# Nixie_Clock_Display_Board_IN14.net
KiCad netlist of a schematic drawn in EAGLE
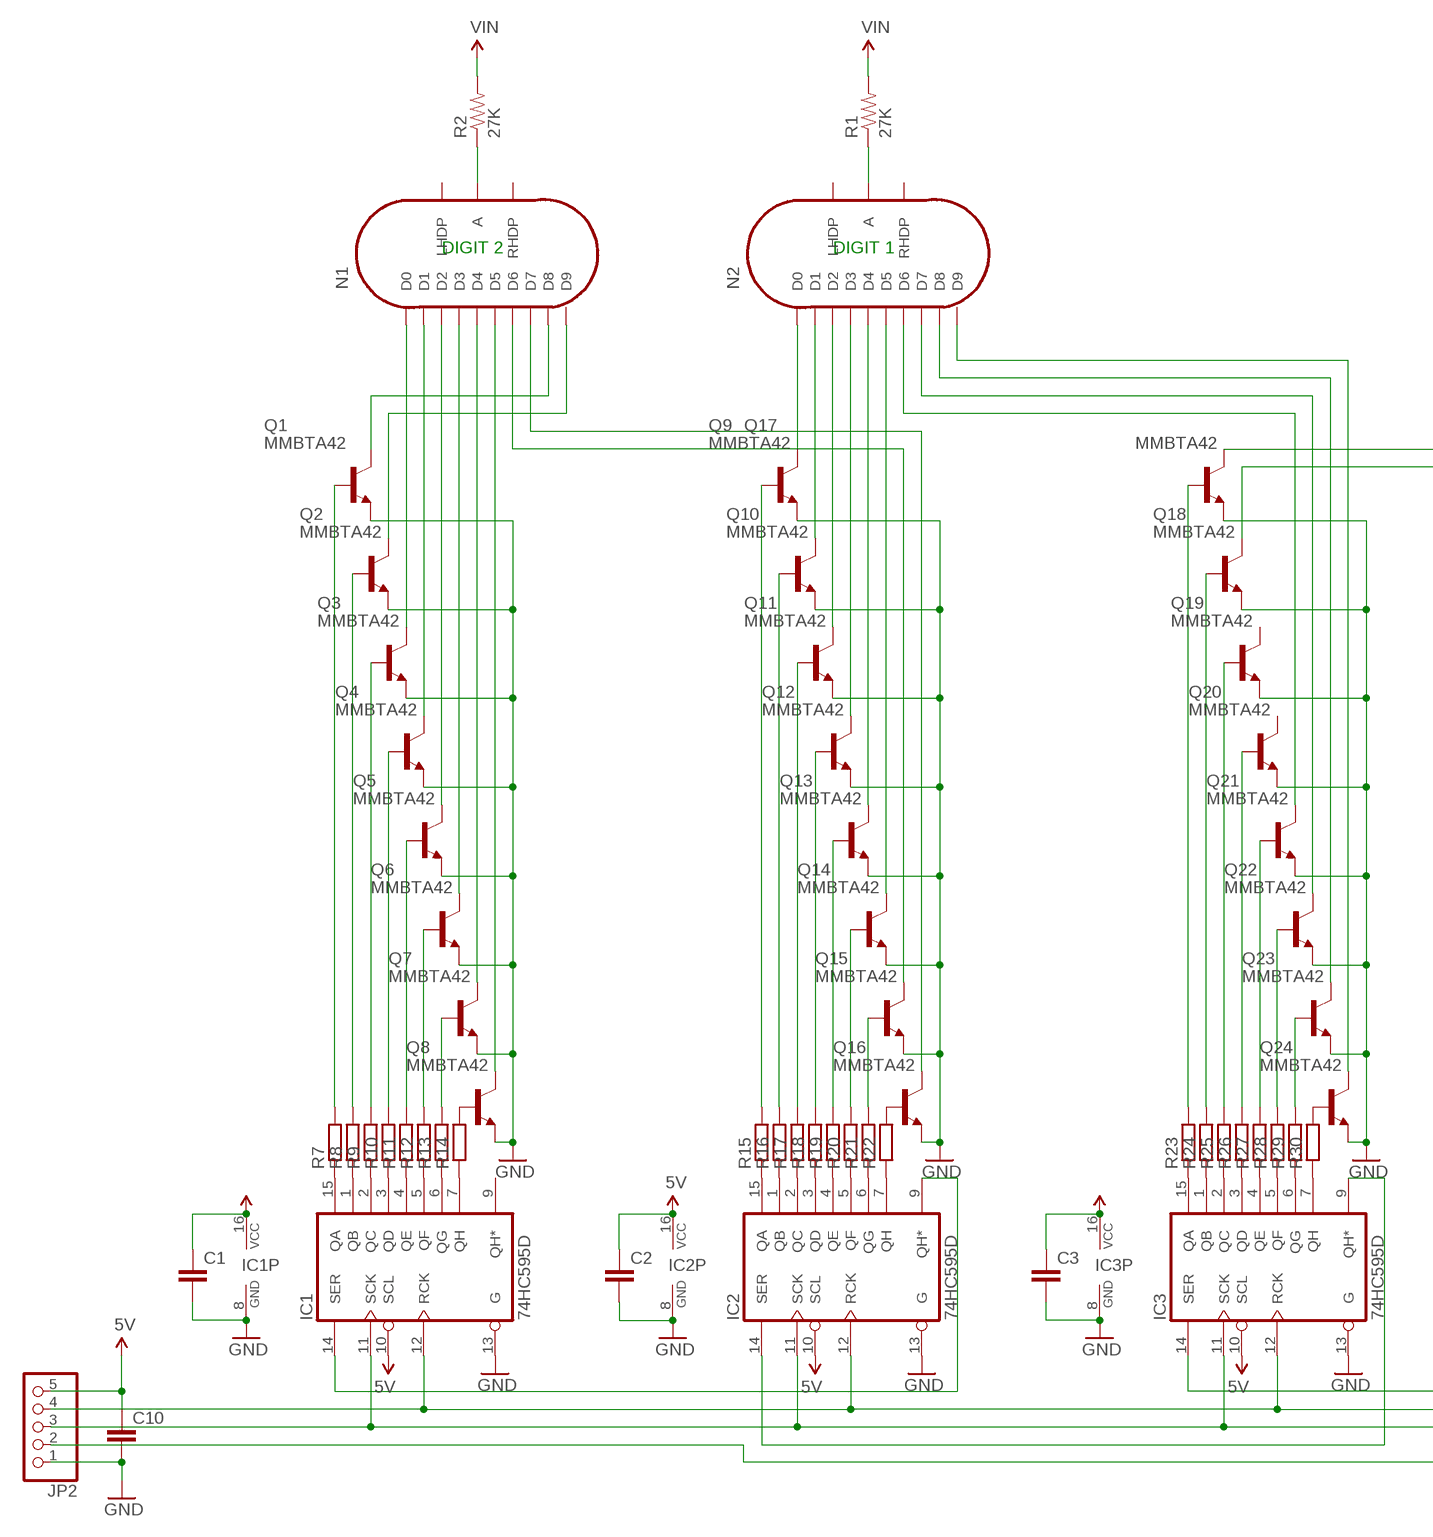
[diagram p0: schematic, sheet 1, part 1 of 2]
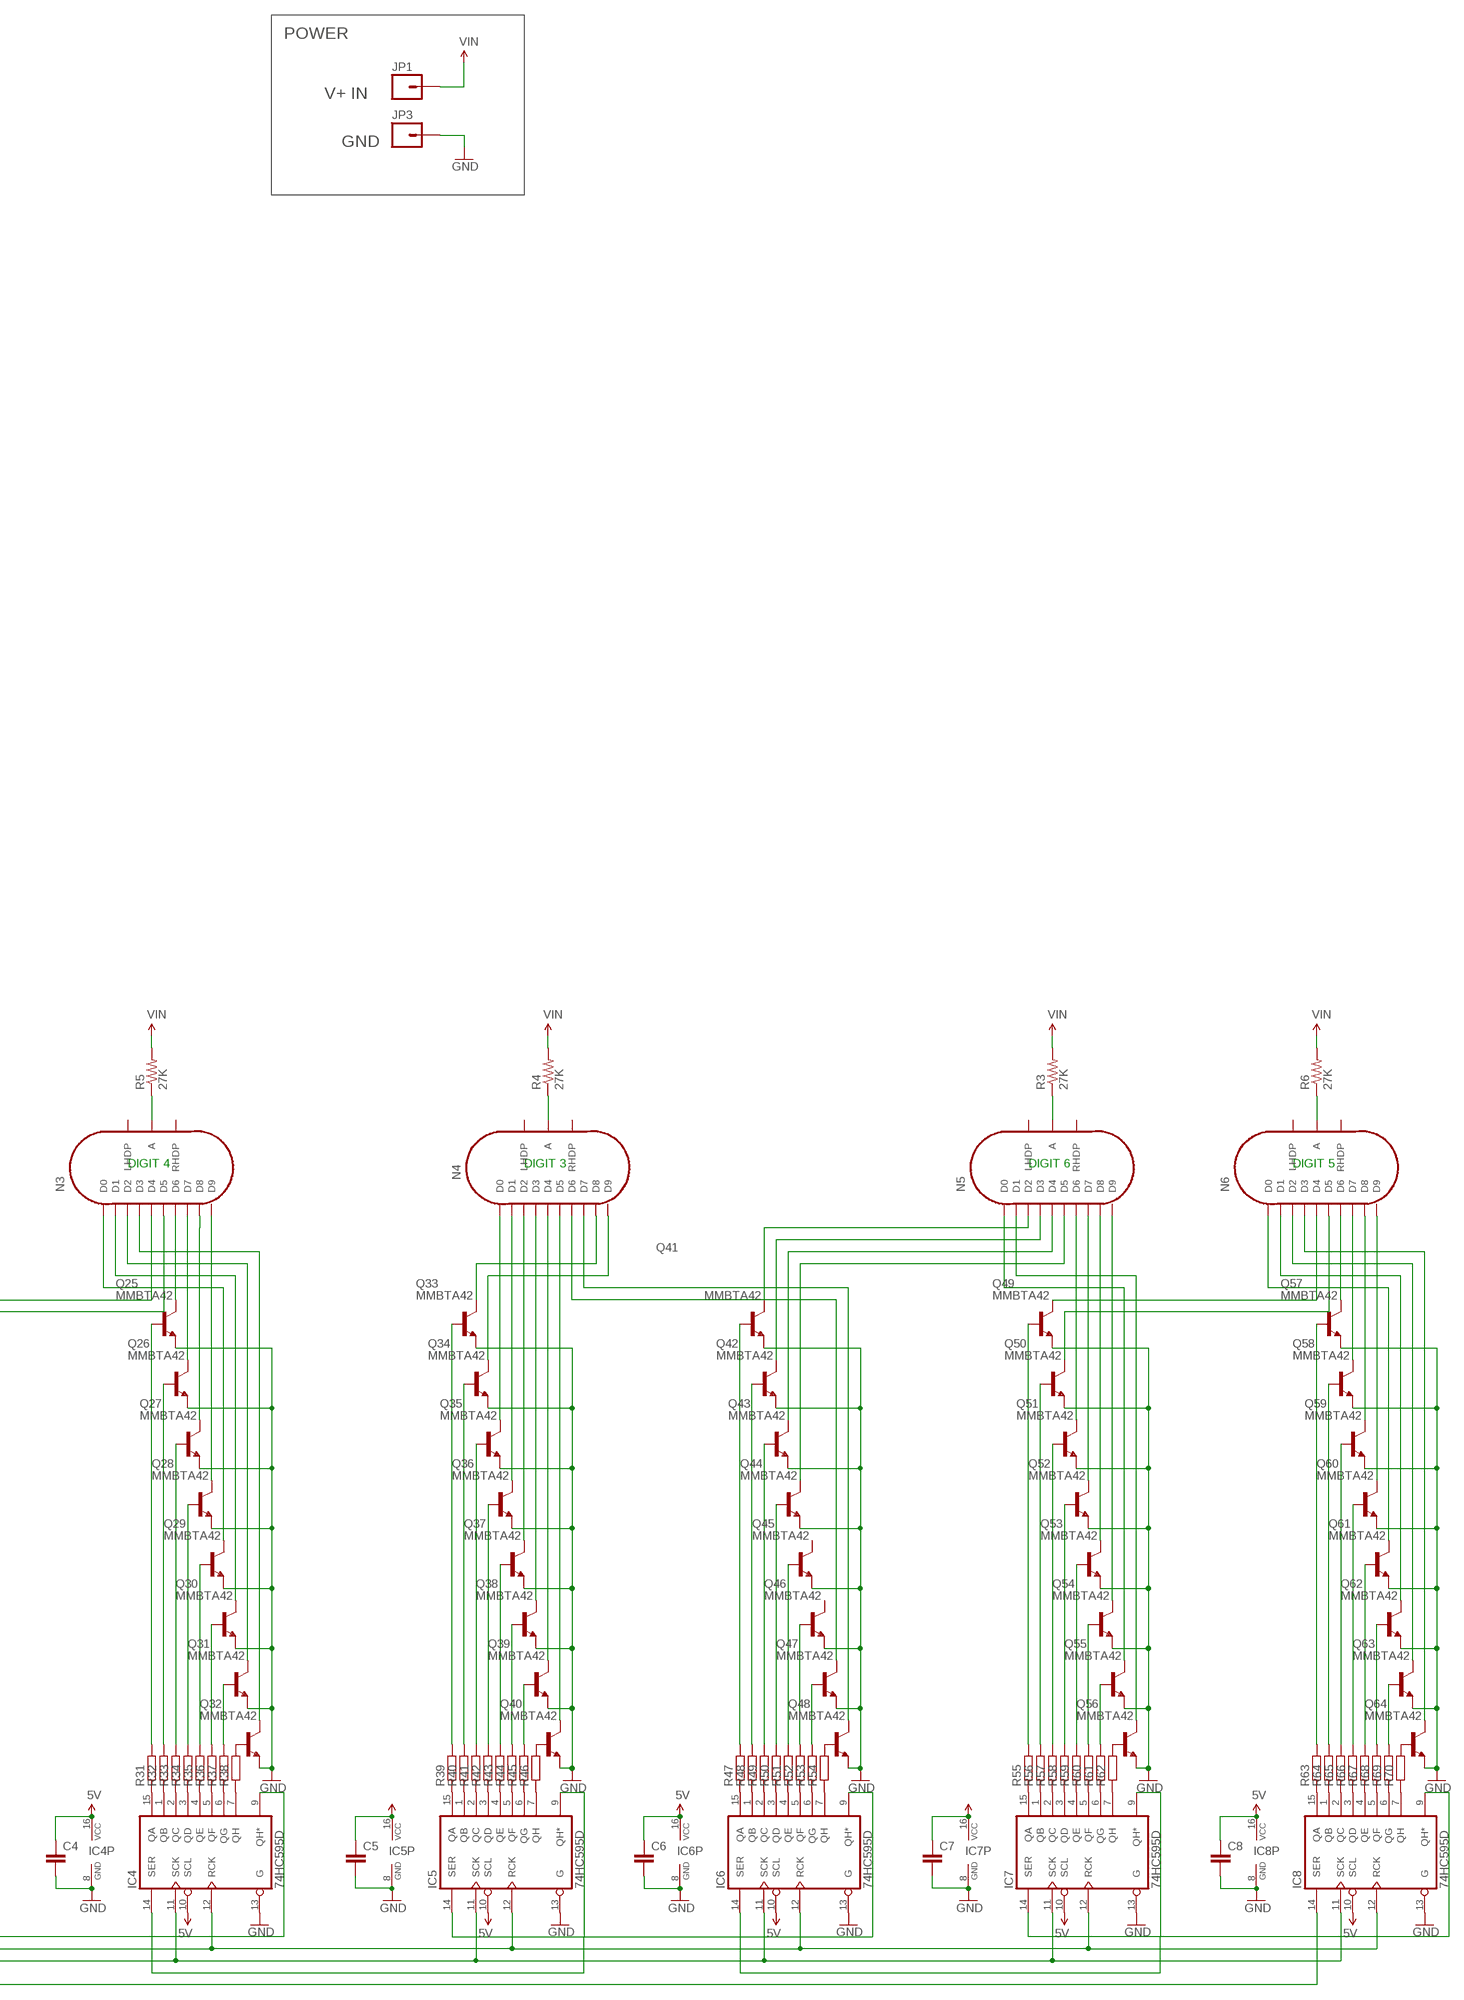
[diagram p1: schematic, sheet 1, part 2 of 2]

(export (version "E")
  (design (tool "Eeschema 10.0.6"))
  (components
    (comp (ref "C1")
      (value "C-EUC0805")
      (footprint "eagle-import:C0805")
      (libsource (lib "eagle-import") (part "C-EUC0805"))
    )
    (comp (ref "C2")
      (value "C-EUC0805")
      (footprint "eagle-import:C0805")
      (libsource (lib "eagle-import") (part "C-EUC0805"))
    )
    (comp (ref "C3")
      (value "C-EUC0805")
      (footprint "eagle-import:C0805")
      (libsource (lib "eagle-import") (part "C-EUC0805"))
    )
    (comp (ref "C4")
      (value "C-EUC0805")
      (footprint "eagle-import:C0805")
      (libsource (lib "eagle-import") (part "C-EUC0805"))
    )
    (comp (ref "C5")
      (value "C-EUC0805")
      (footprint "eagle-import:C0805")
      (libsource (lib "eagle-import") (part "C-EUC0805"))
    )
    (comp (ref "C6")
      (value "C-EUC0805")
      (footprint "eagle-import:C0805")
      (libsource (lib "eagle-import") (part "C-EUC0805"))
    )
    (comp (ref "C7")
      (value "C-EUC0805")
      (footprint "eagle-import:C0805")
      (libsource (lib "eagle-import") (part "C-EUC0805"))
    )
    (comp (ref "C8")
      (value "C-EUC0805")
      (footprint "eagle-import:C0805")
      (libsource (lib "eagle-import") (part "C-EUC0805"))
    )
    (comp (ref "C10")
      (value "C-EUC0805")
      (footprint "eagle-import:C0805")
      (libsource (lib "eagle-import") (part "C-EUC0805"))
    )
    (comp (ref "IC1")
      (value "74HC595D")
      (footprint "eagle-import:SO16")
      (libsource (lib "eagle-import") (part "74595DHC"))
    )
    (comp (ref "IC2")
      (value "74HC595D")
      (footprint "eagle-import:SO16")
      (libsource (lib "eagle-import") (part "74595DHC"))
    )
    (comp (ref "IC3")
      (value "74HC595D")
      (footprint "eagle-import:SO16")
      (libsource (lib "eagle-import") (part "74595DHC"))
    )
    (comp (ref "IC4")
      (value "74HC595D")
      (footprint "eagle-import:SO16")
      (libsource (lib "eagle-import") (part "74595DHC"))
    )
    (comp (ref "IC5")
      (value "74HC595D")
      (footprint "eagle-import:SO16")
      (libsource (lib "eagle-import") (part "74595DHC"))
    )
    (comp (ref "IC6")
      (value "74HC595D")
      (footprint "eagle-import:SO16")
      (libsource (lib "eagle-import") (part "74595DHC"))
    )
    (comp (ref "IC7")
      (value "74HC595D")
      (footprint "eagle-import:SO16")
      (libsource (lib "eagle-import") (part "74595DHC"))
    )
    (comp (ref "IC8")
      (value "74HC595D")
      (footprint "eagle-import:SO16")
      (libsource (lib "eagle-import") (part "74595DHC"))
    )
    (comp (ref "JP1")
      (value "M01PTH")
      (footprint "eagle-import:1X01")
      (libsource (lib "eagle-import") (part "M01PTH"))
    )
    (comp (ref "JP2")
      (value "PINHD-1X5")
      (footprint "eagle-import:1X05")
      (libsource (lib "eagle-import") (part "PINHD-1X5"))
    )
    (comp (ref "JP3")
      (value "M01PTH")
      (footprint "eagle-import:1X01")
      (libsource (lib "eagle-import") (part "M01PTH"))
    )
    (comp (ref "N1")
      (value "IN-14")
      (footprint "eagle-import:IN-14")
      (libsource (lib "eagle-import") (part "IN-14"))
    )
    (comp (ref "N2")
      (value "IN-14")
      (footprint "eagle-import:IN-14")
      (libsource (lib "eagle-import") (part "IN-14"))
    )
    (comp (ref "N3")
      (value "IN-14")
      (footprint "eagle-import:IN-14")
      (libsource (lib "eagle-import") (part "IN-14"))
    )
    (comp (ref "N4")
      (value "IN-14")
      (footprint "eagle-import:IN-14")
      (libsource (lib "eagle-import") (part "IN-14"))
    )
    (comp (ref "N5")
      (value "IN-14")
      (footprint "eagle-import:IN-14")
      (libsource (lib "eagle-import") (part "IN-14"))
    )
    (comp (ref "N6")
      (value "IN-14")
      (footprint "eagle-import:IN-14")
      (libsource (lib "eagle-import") (part "IN-14"))
    )
    (comp (ref "Q1")
      (value "MMBTA42")
      (footprint "eagle-import:SOT23")
      (fields (field (name "MF") "Diotec Semiconductor"))
      (libsource (lib "eagle-import") (part "MMBTA42"))
    )
    (comp (ref "Q2")
      (value "MMBTA42")
      (footprint "eagle-import:SOT23")
      (fields (field (name "MF") "Diotec Semiconductor"))
      (libsource (lib "eagle-import") (part "MMBTA42"))
    )
    (comp (ref "Q3")
      (value "MMBTA42")
      (footprint "eagle-import:SOT23")
      (fields (field (name "MF") "Diotec Semiconductor"))
      (libsource (lib "eagle-import") (part "MMBTA42"))
    )
    (comp (ref "Q4")
      (value "MMBTA42")
      (footprint "eagle-import:SOT23")
      (fields (field (name "MF") "Diotec Semiconductor"))
      (libsource (lib "eagle-import") (part "MMBTA42"))
    )
    (comp (ref "Q5")
      (value "MMBTA42")
      (footprint "eagle-import:SOT23")
      (fields (field (name "MF") "Diotec Semiconductor"))
      (libsource (lib "eagle-import") (part "MMBTA42"))
    )
    (comp (ref "Q6")
      (value "MMBTA42")
      (footprint "eagle-import:SOT23")
      (fields (field (name "MF") "Diotec Semiconductor"))
      (libsource (lib "eagle-import") (part "MMBTA42"))
    )
    (comp (ref "Q7")
      (value "MMBTA42")
      (footprint "eagle-import:SOT23")
      (fields (field (name "MF") "Diotec Semiconductor"))
      (libsource (lib "eagle-import") (part "MMBTA42"))
    )
    (comp (ref "Q8")
      (value "MMBTA42")
      (footprint "eagle-import:SOT23")
      (fields (field (name "MF") "Diotec Semiconductor"))
      (libsource (lib "eagle-import") (part "MMBTA42"))
    )
    (comp (ref "Q9")
      (value "MMBTA42")
      (footprint "eagle-import:SOT23")
      (fields (field (name "MF") "Diotec Semiconductor"))
      (libsource (lib "eagle-import") (part "MMBTA42"))
    )
    (comp (ref "Q10")
      (value "MMBTA42")
      (footprint "eagle-import:SOT23")
      (fields (field (name "MF") "Diotec Semiconductor"))
      (libsource (lib "eagle-import") (part "MMBTA42"))
    )
    (comp (ref "Q11")
      (value "MMBTA42")
      (footprint "eagle-import:SOT23")
      (fields (field (name "MF") "Diotec Semiconductor"))
      (libsource (lib "eagle-import") (part "MMBTA42"))
    )
    (comp (ref "Q12")
      (value "MMBTA42")
      (footprint "eagle-import:SOT23")
      (fields (field (name "MF") "Diotec Semiconductor"))
      (libsource (lib "eagle-import") (part "MMBTA42"))
    )
    (comp (ref "Q13")
      (value "MMBTA42")
      (footprint "eagle-import:SOT23")
      (fields (field (name "MF") "Diotec Semiconductor"))
      (libsource (lib "eagle-import") (part "MMBTA42"))
    )
    (comp (ref "Q14")
      (value "MMBTA42")
      (footprint "eagle-import:SOT23")
      (fields (field (name "MF") "Diotec Semiconductor"))
      (libsource (lib "eagle-import") (part "MMBTA42"))
    )
    (comp (ref "Q15")
      (value "MMBTA42")
      (footprint "eagle-import:SOT23")
      (fields (field (name "MF") "Diotec Semiconductor"))
      (libsource (lib "eagle-import") (part "MMBTA42"))
    )
    (comp (ref "Q16")
      (value "MMBTA42")
      (footprint "eagle-import:SOT23")
      (fields (field (name "MF") "Diotec Semiconductor"))
      (libsource (lib "eagle-import") (part "MMBTA42"))
    )
    (comp (ref "Q17")
      (value "MMBTA42")
      (footprint "eagle-import:SOT23")
      (fields (field (name "MF") "Diotec Semiconductor"))
      (libsource (lib "eagle-import") (part "MMBTA42"))
    )
    (comp (ref "Q18")
      (value "MMBTA42")
      (footprint "eagle-import:SOT23")
      (fields (field (name "MF") "Diotec Semiconductor"))
      (libsource (lib "eagle-import") (part "MMBTA42"))
    )
    (comp (ref "Q19")
      (value "MMBTA42")
      (footprint "eagle-import:SOT23")
      (fields (field (name "MF") "Diotec Semiconductor"))
      (libsource (lib "eagle-import") (part "MMBTA42"))
    )
    (comp (ref "Q20")
      (value "MMBTA42")
      (footprint "eagle-import:SOT23")
      (fields (field (name "MF") "Diotec Semiconductor"))
      (libsource (lib "eagle-import") (part "MMBTA42"))
    )
    (comp (ref "Q21")
      (value "MMBTA42")
      (footprint "eagle-import:SOT23")
      (fields (field (name "MF") "Diotec Semiconductor"))
      (libsource (lib "eagle-import") (part "MMBTA42"))
    )
    (comp (ref "Q22")
      (value "MMBTA42")
      (footprint "eagle-import:SOT23")
      (fields (field (name "MF") "Diotec Semiconductor"))
      (libsource (lib "eagle-import") (part "MMBTA42"))
    )
    (comp (ref "Q23")
      (value "MMBTA42")
      (footprint "eagle-import:SOT23")
      (fields (field (name "MF") "Diotec Semiconductor"))
      (libsource (lib "eagle-import") (part "MMBTA42"))
    )
    (comp (ref "Q24")
      (value "MMBTA42")
      (footprint "eagle-import:SOT23")
      (fields (field (name "MF") "Diotec Semiconductor"))
      (libsource (lib "eagle-import") (part "MMBTA42"))
    )
    (comp (ref "Q25")
      (value "MMBTA42")
      (footprint "eagle-import:SOT23")
      (fields (field (name "MF") "Diotec Semiconductor"))
      (libsource (lib "eagle-import") (part "MMBTA42"))
    )
    (comp (ref "Q26")
      (value "MMBTA42")
      (footprint "eagle-import:SOT23")
      (fields (field (name "MF") "Diotec Semiconductor"))
      (libsource (lib "eagle-import") (part "MMBTA42"))
    )
    (comp (ref "Q27")
      (value "MMBTA42")
      (footprint "eagle-import:SOT23")
      (fields (field (name "MF") "Diotec Semiconductor"))
      (libsource (lib "eagle-import") (part "MMBTA42"))
    )
    (comp (ref "Q28")
      (value "MMBTA42")
      (footprint "eagle-import:SOT23")
      (fields (field (name "MF") "Diotec Semiconductor"))
      (libsource (lib "eagle-import") (part "MMBTA42"))
    )
    (comp (ref "Q29")
      (value "MMBTA42")
      (footprint "eagle-import:SOT23")
      (fields (field (name "MF") "Diotec Semiconductor"))
      (libsource (lib "eagle-import") (part "MMBTA42"))
    )
    (comp (ref "Q30")
      (value "MMBTA42")
      (footprint "eagle-import:SOT23")
      (fields (field (name "MF") "Diotec Semiconductor"))
      (libsource (lib "eagle-import") (part "MMBTA42"))
    )
    (comp (ref "Q31")
      (value "MMBTA42")
      (footprint "eagle-import:SOT23")
      (fields (field (name "MF") "Diotec Semiconductor"))
      (libsource (lib "eagle-import") (part "MMBTA42"))
    )
    (comp (ref "Q32")
      (value "MMBTA42")
      (footprint "eagle-import:SOT23")
      (fields (field (name "MF") "Diotec Semiconductor"))
      (libsource (lib "eagle-import") (part "MMBTA42"))
    )
    (comp (ref "Q33")
      (value "MMBTA42")
      (footprint "eagle-import:SOT23")
      (fields (field (name "MF") "Diotec Semiconductor"))
      (libsource (lib "eagle-import") (part "MMBTA42"))
    )
    (comp (ref "Q34")
      (value "MMBTA42")
      (footprint "eagle-import:SOT23")
      (fields (field (name "MF") "Diotec Semiconductor"))
      (libsource (lib "eagle-import") (part "MMBTA42"))
    )
    (comp (ref "Q35")
      (value "MMBTA42")
      (footprint "eagle-import:SOT23")
      (fields (field (name "MF") "Diotec Semiconductor"))
      (libsource (lib "eagle-import") (part "MMBTA42"))
    )
    (comp (ref "Q36")
      (value "MMBTA42")
      (footprint "eagle-import:SOT23")
      (fields (field (name "MF") "Diotec Semiconductor"))
      (libsource (lib "eagle-import") (part "MMBTA42"))
    )
    (comp (ref "Q37")
      (value "MMBTA42")
      (footprint "eagle-import:SOT23")
      (fields (field (name "MF") "Diotec Semiconductor"))
      (libsource (lib "eagle-import") (part "MMBTA42"))
    )
    (comp (ref "Q38")
      (value "MMBTA42")
      (footprint "eagle-import:SOT23")
      (fields (field (name "MF") "Diotec Semiconductor"))
      (libsource (lib "eagle-import") (part "MMBTA42"))
    )
    (comp (ref "Q39")
      (value "MMBTA42")
      (footprint "eagle-import:SOT23")
      (fields (field (name "MF") "Diotec Semiconductor"))
      (libsource (lib "eagle-import") (part "MMBTA42"))
    )
    (comp (ref "Q40")
      (value "MMBTA42")
      (footprint "eagle-import:SOT23")
      (fields (field (name "MF") "Diotec Semiconductor"))
      (libsource (lib "eagle-import") (part "MMBTA42"))
    )
    (comp (ref "Q41")
      (value "MMBTA42")
      (footprint "eagle-import:SOT23")
      (fields (field (name "MF") "Diotec Semiconductor"))
      (libsource (lib "eagle-import") (part "MMBTA42"))
    )
    (comp (ref "Q42")
      (value "MMBTA42")
      (footprint "eagle-import:SOT23")
      (fields (field (name "MF") "Diotec Semiconductor"))
      (libsource (lib "eagle-import") (part "MMBTA42"))
    )
    (comp (ref "Q43")
      (value "MMBTA42")
      (footprint "eagle-import:SOT23")
      (fields (field (name "MF") "Diotec Semiconductor"))
      (libsource (lib "eagle-import") (part "MMBTA42"))
    )
    (comp (ref "Q44")
      (value "MMBTA42")
      (footprint "eagle-import:SOT23")
      (fields (field (name "MF") "Diotec Semiconductor"))
      (libsource (lib "eagle-import") (part "MMBTA42"))
    )
    (comp (ref "Q45")
      (value "MMBTA42")
      (footprint "eagle-import:SOT23")
      (fields (field (name "MF") "Diotec Semiconductor"))
      (libsource (lib "eagle-import") (part "MMBTA42"))
    )
    (comp (ref "Q46")
      (value "MMBTA42")
      (footprint "eagle-import:SOT23")
      (fields (field (name "MF") "Diotec Semiconductor"))
      (libsource (lib "eagle-import") (part "MMBTA42"))
    )
    (comp (ref "Q47")
      (value "MMBTA42")
      (footprint "eagle-import:SOT23")
      (fields (field (name "MF") "Diotec Semiconductor"))
      (libsource (lib "eagle-import") (part "MMBTA42"))
    )
    (comp (ref "Q48")
      (value "MMBTA42")
      (footprint "eagle-import:SOT23")
      (fields (field (name "MF") "Diotec Semiconductor"))
      (libsource (lib "eagle-import") (part "MMBTA42"))
    )
    (comp (ref "Q49")
      (value "MMBTA42")
      (footprint "eagle-import:SOT23")
      (fields (field (name "MF") "Diotec Semiconductor"))
      (libsource (lib "eagle-import") (part "MMBTA42"))
    )
    (comp (ref "Q50")
      (value "MMBTA42")
      (footprint "eagle-import:SOT23")
      (fields (field (name "MF") "Diotec Semiconductor"))
      (libsource (lib "eagle-import") (part "MMBTA42"))
    )
    (comp (ref "Q51")
      (value "MMBTA42")
      (footprint "eagle-import:SOT23")
      (fields (field (name "MF") "Diotec Semiconductor"))
      (libsource (lib "eagle-import") (part "MMBTA42"))
    )
    (comp (ref "Q52")
      (value "MMBTA42")
      (footprint "eagle-import:SOT23")
      (fields (field (name "MF") "Diotec Semiconductor"))
      (libsource (lib "eagle-import") (part "MMBTA42"))
    )
    (comp (ref "Q53")
      (value "MMBTA42")
      (footprint "eagle-import:SOT23")
      (fields (field (name "MF") "Diotec Semiconductor"))
      (libsource (lib "eagle-import") (part "MMBTA42"))
    )
    (comp (ref "Q54")
      (value "MMBTA42")
      (footprint "eagle-import:SOT23")
      (fields (field (name "MF") "Diotec Semiconductor"))
      (libsource (lib "eagle-import") (part "MMBTA42"))
    )
    (comp (ref "Q55")
      (value "MMBTA42")
      (footprint "eagle-import:SOT23")
      (fields (field (name "MF") "Diotec Semiconductor"))
      (libsource (lib "eagle-import") (part "MMBTA42"))
    )
    (comp (ref "Q56")
      (value "MMBTA42")
      (footprint "eagle-import:SOT23")
      (fields (field (name "MF") "Diotec Semiconductor"))
      (libsource (lib "eagle-import") (part "MMBTA42"))
    )
    (comp (ref "Q57")
      (value "MMBTA42")
      (footprint "eagle-import:SOT23")
      (fields (field (name "MF") "Diotec Semiconductor"))
      (libsource (lib "eagle-import") (part "MMBTA42"))
    )
    (comp (ref "Q58")
      (value "MMBTA42")
      (footprint "eagle-import:SOT23")
      (fields (field (name "MF") "Diotec Semiconductor"))
      (libsource (lib "eagle-import") (part "MMBTA42"))
    )
    (comp (ref "Q59")
      (value "MMBTA42")
      (footprint "eagle-import:SOT23")
      (fields (field (name "MF") "Diotec Semiconductor"))
      (libsource (lib "eagle-import") (part "MMBTA42"))
    )
    (comp (ref "Q60")
      (value "MMBTA42")
      (footprint "eagle-import:SOT23")
      (fields (field (name "MF") "Diotec Semiconductor"))
      (libsource (lib "eagle-import") (part "MMBTA42"))
    )
    (comp (ref "Q61")
      (value "MMBTA42")
      (footprint "eagle-import:SOT23")
      (fields (field (name "MF") "Diotec Semiconductor"))
      (libsource (lib "eagle-import") (part "MMBTA42"))
    )
    (comp (ref "Q62")
      (value "MMBTA42")
      (footprint "eagle-import:SOT23")
      (fields (field (name "MF") "Diotec Semiconductor"))
      (libsource (lib "eagle-import") (part "MMBTA42"))
    )
    (comp (ref "Q63")
      (value "MMBTA42")
      (footprint "eagle-import:SOT23")
      (fields (field (name "MF") "Diotec Semiconductor"))
      (libsource (lib "eagle-import") (part "MMBTA42"))
    )
    (comp (ref "Q64")
      (value "MMBTA42")
      (footprint "eagle-import:SOT23")
      (fields (field (name "MF") "Diotec Semiconductor"))
      (libsource (lib "eagle-import") (part "MMBTA42"))
    )
    (comp (ref "R1")
      (value "27K")
      (footprint "eagle-import:AXIAL-0.5")
      (libsource (lib "eagle-import") (part "RESISTORPTH-1/2W"))
    )
    (comp (ref "R2")
      (value "27K")
      (footprint "eagle-import:AXIAL-0.5")
      (libsource (lib "eagle-import") (part "RESISTORPTH-1/2W"))
    )
    (comp (ref "R3")
      (value "27K")
      (footprint "eagle-import:AXIAL-0.5")
      (libsource (lib "eagle-import") (part "RESISTORPTH-1/2W"))
    )
    (comp (ref "R4")
      (value "27K")
      (footprint "eagle-import:AXIAL-0.5")
      (libsource (lib "eagle-import") (part "RESISTORPTH-1/2W"))
    )
    (comp (ref "R5")
      (value "27K")
      (footprint "eagle-import:AXIAL-0.5")
      (libsource (lib "eagle-import") (part "RESISTORPTH-1/2W"))
    )
    (comp (ref "R6")
      (value "27K")
      (footprint "eagle-import:AXIAL-0.5")
      (libsource (lib "eagle-import") (part "RESISTORPTH-1/2W"))
    )
    (comp (ref "R7")
      (value "R-EU_R0805")
      (footprint "eagle-import:R0805")
      (libsource (lib "eagle-import") (part "R-EU_R0805"))
    )
    (comp (ref "R8")
      (value "R-EU_R0805")
      (footprint "eagle-import:R0805")
      (libsource (lib "eagle-import") (part "R-EU_R0805"))
    )
    (comp (ref "R9")
      (value "R-EU_R0805")
      (footprint "eagle-import:R0805")
      (libsource (lib "eagle-import") (part "R-EU_R0805"))
    )
    (comp (ref "R10")
      (value "R-EU_R0805")
      (footprint "eagle-import:R0805")
      (libsource (lib "eagle-import") (part "R-EU_R0805"))
    )
    (comp (ref "R11")
      (value "R-EU_R0805")
      (footprint "eagle-import:R0805")
      (libsource (lib "eagle-import") (part "R-EU_R0805"))
    )
    (comp (ref "R12")
      (value "R-EU_R0805")
      (footprint "eagle-import:R0805")
      (libsource (lib "eagle-import") (part "R-EU_R0805"))
    )
    (comp (ref "R13")
      (value "R-EU_R0805")
      (footprint "eagle-import:R0805")
      (libsource (lib "eagle-import") (part "R-EU_R0805"))
    )
    (comp (ref "R14")
      (value "R-EU_R0805")
      (footprint "eagle-import:R0805")
      (libsource (lib "eagle-import") (part "R-EU_R0805"))
    )
    (comp (ref "R15")
      (value "R-EU_R0805")
      (footprint "eagle-import:R0805")
      (libsource (lib "eagle-import") (part "R-EU_R0805"))
    )
    (comp (ref "R16")
      (value "R-EU_R0805")
      (footprint "eagle-import:R0805")
      (libsource (lib "eagle-import") (part "R-EU_R0805"))
    )
    (comp (ref "R17")
      (value "R-EU_R0805")
      (footprint "eagle-import:R0805")
      (libsource (lib "eagle-import") (part "R-EU_R0805"))
    )
    (comp (ref "R18")
      (value "R-EU_R0805")
      (footprint "eagle-import:R0805")
      (libsource (lib "eagle-import") (part "R-EU_R0805"))
    )
    (comp (ref "R19")
      (value "R-EU_R0805")
      (footprint "eagle-import:R0805")
      (libsource (lib "eagle-import") (part "R-EU_R0805"))
    )
    (comp (ref "R20")
      (value "R-EU_R0805")
      (footprint "eagle-import:R0805")
      (libsource (lib "eagle-import") (part "R-EU_R0805"))
    )
    (comp (ref "R21")
      (value "R-EU_R0805")
      (footprint "eagle-import:R0805")
      (libsource (lib "eagle-import") (part "R-EU_R0805"))
    )
    (comp (ref "R22")
      (value "R-EU_R0805")
      (footprint "eagle-import:R0805")
      (libsource (lib "eagle-import") (part "R-EU_R0805"))
    )
    (comp (ref "R23")
      (value "R-EU_R0805")
      (footprint "eagle-import:R0805")
      (libsource (lib "eagle-import") (part "R-EU_R0805"))
    )
    (comp (ref "R24")
      (value "R-EU_R0805")
      (footprint "eagle-import:R0805")
      (libsource (lib "eagle-import") (part "R-EU_R0805"))
    )
    (comp (ref "R25")
      (value "R-EU_R0805")
      (footprint "eagle-import:R0805")
      (libsource (lib "eagle-import") (part "R-EU_R0805"))
    )
    (comp (ref "R26")
      (value "R-EU_R0805")
      (footprint "eagle-import:R0805")
      (libsource (lib "eagle-import") (part "R-EU_R0805"))
    )
    (comp (ref "R27")
      (value "R-EU_R0805")
      (footprint "eagle-import:R0805")
      (libsource (lib "eagle-import") (part "R-EU_R0805"))
    )
    (comp (ref "R28")
      (value "R-EU_R0805")
      (footprint "eagle-import:R0805")
      (libsource (lib "eagle-import") (part "R-EU_R0805"))
    )
    (comp (ref "R29")
      (value "R-EU_R0805")
      (footprint "eagle-import:R0805")
      (libsource (lib "eagle-import") (part "R-EU_R0805"))
    )
    (comp (ref "R30")
      (value "R-EU_R0805")
      (footprint "eagle-import:R0805")
      (libsource (lib "eagle-import") (part "R-EU_R0805"))
    )
    (comp (ref "R31")
      (value "R-EU_R0805")
      (footprint "eagle-import:R0805")
      (libsource (lib "eagle-import") (part "R-EU_R0805"))
    )
    (comp (ref "R32")
      (value "R-EU_R0805")
      (footprint "eagle-import:R0805")
      (libsource (lib "eagle-import") (part "R-EU_R0805"))
    )
    (comp (ref "R33")
      (value "R-EU_R0805")
      (footprint "eagle-import:R0805")
      (libsource (lib "eagle-import") (part "R-EU_R0805"))
    )
    (comp (ref "R34")
      (value "R-EU_R0805")
      (footprint "eagle-import:R0805")
      (libsource (lib "eagle-import") (part "R-EU_R0805"))
    )
    (comp (ref "R35")
      (value "R-EU_R0805")
      (footprint "eagle-import:R0805")
      (libsource (lib "eagle-import") (part "R-EU_R0805"))
    )
    (comp (ref "R36")
      (value "R-EU_R0805")
      (footprint "eagle-import:R0805")
      (libsource (lib "eagle-import") (part "R-EU_R0805"))
    )
    (comp (ref "R37")
      (value "R-EU_R0805")
      (footprint "eagle-import:R0805")
      (libsource (lib "eagle-import") (part "R-EU_R0805"))
    )
    (comp (ref "R38")
      (value "R-EU_R0805")
      (footprint "eagle-import:R0805")
      (libsource (lib "eagle-import") (part "R-EU_R0805"))
    )
    (comp (ref "R39")
      (value "R-EU_R0805")
      (footprint "eagle-import:R0805")
      (libsource (lib "eagle-import") (part "R-EU_R0805"))
    )
    (comp (ref "R40")
      (value "R-EU_R0805")
      (footprint "eagle-import:R0805")
      (libsource (lib "eagle-import") (part "R-EU_R0805"))
    )
    (comp (ref "R41")
      (value "R-EU_R0805")
      (footprint "eagle-import:R0805")
      (libsource (lib "eagle-import") (part "R-EU_R0805"))
    )
    (comp (ref "R42")
      (value "R-EU_R0805")
      (footprint "eagle-import:R0805")
      (libsource (lib "eagle-import") (part "R-EU_R0805"))
    )
    (comp (ref "R43")
      (value "R-EU_R0805")
      (footprint "eagle-import:R0805")
      (libsource (lib "eagle-import") (part "R-EU_R0805"))
    )
    (comp (ref "R44")
      (value "R-EU_R0805")
      (footprint "eagle-import:R0805")
      (libsource (lib "eagle-import") (part "R-EU_R0805"))
    )
    (comp (ref "R45")
      (value "R-EU_R0805")
      (footprint "eagle-import:R0805")
      (libsource (lib "eagle-import") (part "R-EU_R0805"))
    )
    (comp (ref "R46")
      (value "R-EU_R0805")
      (footprint "eagle-import:R0805")
      (libsource (lib "eagle-import") (part "R-EU_R0805"))
    )
    (comp (ref "R47")
      (value "R-EU_R0805")
      (footprint "eagle-import:R0805")
      (libsource (lib "eagle-import") (part "R-EU_R0805"))
    )
    (comp (ref "R48")
      (value "R-EU_R0805")
      (footprint "eagle-import:R0805")
      (libsource (lib "eagle-import") (part "R-EU_R0805"))
    )
    (comp (ref "R49")
      (value "R-EU_R0805")
      (footprint "eagle-import:R0805")
      (libsource (lib "eagle-import") (part "R-EU_R0805"))
    )
    (comp (ref "R50")
      (value "R-EU_R0805")
      (footprint "eagle-import:R0805")
      (libsource (lib "eagle-import") (part "R-EU_R0805"))
    )
    (comp (ref "R51")
      (value "R-EU_R0805")
      (footprint "eagle-import:R0805")
      (libsource (lib "eagle-import") (part "R-EU_R0805"))
    )
    (comp (ref "R52")
      (value "R-EU_R0805")
      (footprint "eagle-import:R0805")
      (libsource (lib "eagle-import") (part "R-EU_R0805"))
    )
    (comp (ref "R53")
      (value "R-EU_R0805")
      (footprint "eagle-import:R0805")
      (libsource (lib "eagle-import") (part "R-EU_R0805"))
    )
    (comp (ref "R54")
      (value "R-EU_R0805")
      (footprint "eagle-import:R0805")
      (libsource (lib "eagle-import") (part "R-EU_R0805"))
    )
    (comp (ref "R55")
      (value "R-EU_R0805")
      (footprint "eagle-import:R0805")
      (libsource (lib "eagle-import") (part "R-EU_R0805"))
    )
    (comp (ref "R56")
      (value "R-EU_R0805")
      (footprint "eagle-import:R0805")
      (libsource (lib "eagle-import") (part "R-EU_R0805"))
    )
    (comp (ref "R57")
      (value "R-EU_R0805")
      (footprint "eagle-import:R0805")
      (libsource (lib "eagle-import") (part "R-EU_R0805"))
    )
    (comp (ref "R58")
      (value "R-EU_R0805")
      (footprint "eagle-import:R0805")
      (libsource (lib "eagle-import") (part "R-EU_R0805"))
    )
    (comp (ref "R59")
      (value "R-EU_R0805")
      (footprint "eagle-import:R0805")
      (libsource (lib "eagle-import") (part "R-EU_R0805"))
    )
    (comp (ref "R60")
      (value "R-EU_R0805")
      (footprint "eagle-import:R0805")
      (libsource (lib "eagle-import") (part "R-EU_R0805"))
    )
    (comp (ref "R61")
      (value "R-EU_R0805")
      (footprint "eagle-import:R0805")
      (libsource (lib "eagle-import") (part "R-EU_R0805"))
    )
    (comp (ref "R62")
      (value "R-EU_R0805")
      (footprint "eagle-import:R0805")
      (libsource (lib "eagle-import") (part "R-EU_R0805"))
    )
    (comp (ref "R63")
      (value "R-EU_R0805")
      (footprint "eagle-import:R0805")
      (libsource (lib "eagle-import") (part "R-EU_R0805"))
    )
    (comp (ref "R64")
      (value "R-EU_R0805")
      (footprint "eagle-import:R0805")
      (libsource (lib "eagle-import") (part "R-EU_R0805"))
    )
    (comp (ref "R65")
      (value "R-EU_R0805")
      (footprint "eagle-import:R0805")
      (libsource (lib "eagle-import") (part "R-EU_R0805"))
    )
    (comp (ref "R66")
      (value "R-EU_R0805")
      (footprint "eagle-import:R0805")
      (libsource (lib "eagle-import") (part "R-EU_R0805"))
    )
    (comp (ref "R67")
      (value "R-EU_R0805")
      (footprint "eagle-import:R0805")
      (libsource (lib "eagle-import") (part "R-EU_R0805"))
    )
    (comp (ref "R68")
      (value "R-EU_R0805")
      (footprint "eagle-import:R0805")
      (libsource (lib "eagle-import") (part "R-EU_R0805"))
    )
    (comp (ref "R69")
      (value "R-EU_R0805")
      (footprint "eagle-import:R0805")
      (libsource (lib "eagle-import") (part "R-EU_R0805"))
    )
    (comp (ref "R70")
      (value "R-EU_R0805")
      (footprint "eagle-import:R0805")
      (libsource (lib "eagle-import") (part "R-EU_R0805"))
    )
  )
  (nets
    (net (code "1") (name "5V") (class "Default")
      (node (ref "C1") (pin "1") (pinfunction "1_1") (pintype "passive"))
      (node (ref "C10") (pin "1") (pinfunction "1_1") (pintype "passive"))
      (node (ref "C2") (pin "1") (pinfunction "1_1") (pintype "passive"))
      (node (ref "C3") (pin "1") (pinfunction "1_1") (pintype "passive"))
      (node (ref "C4") (pin "1") (pinfunction "1_1") (pintype "passive"))
      (node (ref "C5") (pin "1") (pinfunction "1_1") (pintype "passive"))
      (node (ref "C6") (pin "1") (pinfunction "1_1") (pintype "passive"))
      (node (ref "C7") (pin "1") (pinfunction "1_1") (pintype "passive"))
      (node (ref "C8") (pin "1") (pinfunction "1_1") (pintype "passive"))
      (node (ref "IC1") (pin "10") (pinfunction "SCL_10") (pintype "input"))
      (node (ref "IC1") (pin "16") (pinfunction "VCC_16") (pintype "power_in"))
      (node (ref "IC2") (pin "10") (pinfunction "SCL_10") (pintype "input"))
      (node (ref "IC2") (pin "16") (pinfunction "VCC_16") (pintype "power_in"))
      (node (ref "IC3") (pin "10") (pinfunction "SCL_10") (pintype "input"))
      (node (ref "IC3") (pin "16") (pinfunction "VCC_16") (pintype "power_in"))
      (node (ref "IC4") (pin "10") (pinfunction "SCL_10") (pintype "input"))
      (node (ref "IC4") (pin "16") (pinfunction "VCC_16") (pintype "power_in"))
      (node (ref "IC5") (pin "10") (pinfunction "SCL_10") (pintype "input"))
      (node (ref "IC5") (pin "16") (pinfunction "VCC_16") (pintype "power_in"))
      (node (ref "IC6") (pin "10") (pinfunction "SCL_10") (pintype "input"))
      (node (ref "IC6") (pin "16") (pinfunction "VCC_16") (pintype "power_in"))
      (node (ref "IC7") (pin "10") (pinfunction "SCL_10") (pintype "input"))
      (node (ref "IC7") (pin "16") (pinfunction "VCC_16") (pintype "power_in"))
      (node (ref "IC8") (pin "10") (pinfunction "SCL_10") (pintype "input"))
      (node (ref "IC8") (pin "16") (pinfunction "VCC_16") (pintype "power_in"))
      (node (ref "JP2") (pin "5") (pinfunction "5_5") (pintype "passive"))
    )
    (net (code "2") (name "GND") (class "Default")
      (node (ref "C1") (pin "2") (pinfunction "2_2") (pintype "passive"))
      (node (ref "C10") (pin "2") (pinfunction "2_2") (pintype "passive"))
      (node (ref "C2") (pin "2") (pinfunction "2_2") (pintype "passive"))
      (node (ref "C3") (pin "2") (pinfunction "2_2") (pintype "passive"))
      (node (ref "C4") (pin "2") (pinfunction "2_2") (pintype "passive"))
      (node (ref "C5") (pin "2") (pinfunction "2_2") (pintype "passive"))
      (node (ref "C6") (pin "2") (pinfunction "2_2") (pintype "passive"))
      (node (ref "C7") (pin "2") (pinfunction "2_2") (pintype "passive"))
      (node (ref "C8") (pin "2") (pinfunction "2_2") (pintype "passive"))
      (node (ref "IC1") (pin "13") (pinfunction "G_13") (pintype "input"))
      (node (ref "IC1") (pin "8") (pinfunction "GND_8") (pintype "power_in"))
      (node (ref "IC2") (pin "13") (pinfunction "G_13") (pintype "input"))
      (node (ref "IC2") (pin "8") (pinfunction "GND_8") (pintype "power_in"))
      (node (ref "IC3") (pin "13") (pinfunction "G_13") (pintype "input"))
      (node (ref "IC3") (pin "8") (pinfunction "GND_8") (pintype "power_in"))
      (node (ref "IC4") (pin "13") (pinfunction "G_13") (pintype "input"))
      (node (ref "IC4") (pin "8") (pinfunction "GND_8") (pintype "power_in"))
      (node (ref "IC5") (pin "13") (pinfunction "G_13") (pintype "input"))
      (node (ref "IC5") (pin "8") (pinfunction "GND_8") (pintype "power_in"))
      (node (ref "IC6") (pin "13") (pinfunction "G_13") (pintype "input"))
      (node (ref "IC6") (pin "8") (pinfunction "GND_8") (pintype "power_in"))
      (node (ref "IC7") (pin "13") (pinfunction "G_13") (pintype "input"))
      (node (ref "IC7") (pin "8") (pinfunction "GND_8") (pintype "power_in"))
      (node (ref "IC8") (pin "13") (pinfunction "G_13") (pintype "input"))
      (node (ref "IC8") (pin "8") (pinfunction "GND_8") (pintype "power_in"))
      (node (ref "JP2") (pin "1") (pinfunction "1_1") (pintype "passive"))
      (node (ref "JP3") (pin "1") (pinfunction "1_1") (pintype "passive"))
      (node (ref "Q1") (pin "2") (pinfunction "E_2") (pintype "passive"))
      (node (ref "Q10") (pin "2") (pinfunction "E_2") (pintype "passive"))
      (node (ref "Q11") (pin "2") (pinfunction "E_2") (pintype "passive"))
      (node (ref "Q12") (pin "2") (pinfunction "E_2") (pintype "passive"))
      (node (ref "Q13") (pin "2") (pinfunction "E_2") (pintype "passive"))
      (node (ref "Q14") (pin "2") (pinfunction "E_2") (pintype "passive"))
      (node (ref "Q15") (pin "2") (pinfunction "E_2") (pintype "passive"))
      (node (ref "Q16") (pin "2") (pinfunction "E_2") (pintype "passive"))
      (node (ref "Q17") (pin "2") (pinfunction "E_2") (pintype "passive"))
      (node (ref "Q18") (pin "2") (pinfunction "E_2") (pintype "passive"))
      (node (ref "Q19") (pin "2") (pinfunction "E_2") (pintype "passive"))
      (node (ref "Q2") (pin "2") (pinfunction "E_2") (pintype "passive"))
      (node (ref "Q20") (pin "2") (pinfunction "E_2") (pintype "passive"))
      (node (ref "Q21") (pin "2") (pinfunction "E_2") (pintype "passive"))
      (node (ref "Q22") (pin "2") (pinfunction "E_2") (pintype "passive"))
      (node (ref "Q23") (pin "2") (pinfunction "E_2") (pintype "passive"))
      (node (ref "Q24") (pin "2") (pinfunction "E_2") (pintype "passive"))
      (node (ref "Q25") (pin "2") (pinfunction "E_2") (pintype "passive"))
      (node (ref "Q26") (pin "2") (pinfunction "E_2") (pintype "passive"))
      (node (ref "Q27") (pin "2") (pinfunction "E_2") (pintype "passive"))
      (node (ref "Q28") (pin "2") (pinfunction "E_2") (pintype "passive"))
      (node (ref "Q29") (pin "2") (pinfunction "E_2") (pintype "passive"))
      (node (ref "Q3") (pin "2") (pinfunction "E_2") (pintype "passive"))
      (node (ref "Q30") (pin "2") (pinfunction "E_2") (pintype "passive"))
      (node (ref "Q31") (pin "2") (pinfunction "E_2") (pintype "passive"))
      (node (ref "Q32") (pin "2") (pinfunction "E_2") (pintype "passive"))
      (node (ref "Q33") (pin "2") (pinfunction "E_2") (pintype "passive"))
      (node (ref "Q34") (pin "2") (pinfunction "E_2") (pintype "passive"))
      (node (ref "Q35") (pin "2") (pinfunction "E_2") (pintype "passive"))
      (node (ref "Q36") (pin "2") (pinfunction "E_2") (pintype "passive"))
      (node (ref "Q37") (pin "2") (pinfunction "E_2") (pintype "passive"))
      (node (ref "Q38") (pin "2") (pinfunction "E_2") (pintype "passive"))
      (node (ref "Q39") (pin "2") (pinfunction "E_2") (pintype "passive"))
      (node (ref "Q4") (pin "2") (pinfunction "E_2") (pintype "passive"))
      (node (ref "Q40") (pin "2") (pinfunction "E_2") (pintype "passive"))
      (node (ref "Q41") (pin "2") (pinfunction "E_2") (pintype "passive"))
      (node (ref "Q42") (pin "2") (pinfunction "E_2") (pintype "passive"))
      (node (ref "Q43") (pin "2") (pinfunction "E_2") (pintype "passive"))
      (node (ref "Q44") (pin "2") (pinfunction "E_2") (pintype "passive"))
      (node (ref "Q45") (pin "2") (pinfunction "E_2") (pintype "passive"))
      (node (ref "Q46") (pin "2") (pinfunction "E_2") (pintype "passive"))
      (node (ref "Q47") (pin "2") (pinfunction "E_2") (pintype "passive"))
      (node (ref "Q48") (pin "2") (pinfunction "E_2") (pintype "passive"))
      (node (ref "Q49") (pin "2") (pinfunction "E_2") (pintype "passive"))
      (node (ref "Q5") (pin "2") (pinfunction "E_2") (pintype "passive"))
      (node (ref "Q50") (pin "2") (pinfunction "E_2") (pintype "passive"))
      (node (ref "Q51") (pin "2") (pinfunction "E_2") (pintype "passive"))
      (node (ref "Q52") (pin "2") (pinfunction "E_2") (pintype "passive"))
      (node (ref "Q53") (pin "2") (pinfunction "E_2") (pintype "passive"))
      (node (ref "Q54") (pin "2") (pinfunction "E_2") (pintype "passive"))
      (node (ref "Q55") (pin "2") (pinfunction "E_2") (pintype "passive"))
      (node (ref "Q56") (pin "2") (pinfunction "E_2") (pintype "passive"))
      (node (ref "Q57") (pin "2") (pinfunction "E_2") (pintype "passive"))
      (node (ref "Q58") (pin "2") (pinfunction "E_2") (pintype "passive"))
      (node (ref "Q59") (pin "2") (pinfunction "E_2") (pintype "passive"))
      (node (ref "Q6") (pin "2") (pinfunction "E_2") (pintype "passive"))
      (node (ref "Q60") (pin "2") (pinfunction "E_2") (pintype "passive"))
      (node (ref "Q61") (pin "2") (pinfunction "E_2") (pintype "passive"))
      (node (ref "Q62") (pin "2") (pinfunction "E_2") (pintype "passive"))
      (node (ref "Q63") (pin "2") (pinfunction "E_2") (pintype "passive"))
      (node (ref "Q64") (pin "2") (pinfunction "E_2") (pintype "passive"))
      (node (ref "Q7") (pin "2") (pinfunction "E_2") (pintype "passive"))
      (node (ref "Q8") (pin "2") (pinfunction "E_2") (pintype "passive"))
      (node (ref "Q9") (pin "2") (pinfunction "E_2") (pintype "passive"))
    )
    (net (code "3") (name "Net-(IC1A-QA)") (class "Default")
      (node (ref "IC1") (pin "15") (pinfunction "QA_15") (pintype "tri_state"))
      (node (ref "R7") (pin "1") (pinfunction "1_1") (pintype "passive"))
    )
    (net (code "4") (name "Net-(IC1A-QB)") (class "Default")
      (node (ref "IC1") (pin "1") (pinfunction "QB_1") (pintype "tri_state"))
      (node (ref "R8") (pin "1") (pinfunction "1_1") (pintype "passive"))
    )
    (net (code "5") (name "Net-(IC1A-QC)") (class "Default")
      (node (ref "IC1") (pin "2") (pinfunction "QC_2") (pintype "tri_state"))
      (node (ref "R9") (pin "1") (pinfunction "1_1") (pintype "passive"))
    )
    (net (code "6") (name "Net-(IC1A-QD)") (class "Default")
      (node (ref "IC1") (pin "3") (pinfunction "QD_3") (pintype "tri_state"))
      (node (ref "R10") (pin "1") (pinfunction "1_1") (pintype "passive"))
    )
    (net (code "7") (name "Net-(IC1A-QE)") (class "Default")
      (node (ref "IC1") (pin "4") (pinfunction "QE_4") (pintype "tri_state"))
      (node (ref "R11") (pin "1") (pinfunction "1_1") (pintype "passive"))
    )
    (net (code "8") (name "Net-(IC1A-QF)") (class "Default")
      (node (ref "IC1") (pin "5") (pinfunction "QF_5") (pintype "tri_state"))
      (node (ref "R12") (pin "1") (pinfunction "1_1") (pintype "passive"))
    )
    (net (code "9") (name "Net-(IC1A-QG)") (class "Default")
      (node (ref "IC1") (pin "6") (pinfunction "QG_6") (pintype "tri_state"))
      (node (ref "R13") (pin "1") (pinfunction "1_1") (pintype "passive"))
    )
    (net (code "10") (name "Net-(IC1A-QH)") (class "Default")
      (node (ref "IC1") (pin "7") (pinfunction "QH_7") (pintype "tri_state"))
      (node (ref "R14") (pin "1") (pinfunction "1_1") (pintype "passive"))
    )
    (net (code "11") (name "Net-(IC1A-RCK)") (class "Default")
      (node (ref "IC1") (pin "12") (pinfunction "RCK_12") (pintype "input"))
      (node (ref "IC2") (pin "12") (pinfunction "RCK_12") (pintype "input"))
      (node (ref "IC3") (pin "12") (pinfunction "RCK_12") (pintype "input"))
      (node (ref "IC4") (pin "12") (pinfunction "RCK_12") (pintype "input"))
      (node (ref "IC5") (pin "12") (pinfunction "RCK_12") (pintype "input"))
      (node (ref "IC6") (pin "12") (pinfunction "RCK_12") (pintype "input"))
      (node (ref "IC7") (pin "12") (pinfunction "RCK_12") (pintype "input"))
      (node (ref "IC8") (pin "12") (pinfunction "RCK_12") (pintype "input"))
      (node (ref "JP2") (pin "4") (pinfunction "4_4") (pintype "passive"))
    )
    (net (code "12") (name "Net-(IC1A-SCK)") (class "Default")
      (node (ref "IC1") (pin "11") (pinfunction "SCK_11") (pintype "input"))
      (node (ref "IC2") (pin "11") (pinfunction "SCK_11") (pintype "input"))
      (node (ref "IC3") (pin "11") (pinfunction "SCK_11") (pintype "input"))
      (node (ref "IC4") (pin "11") (pinfunction "SCK_11") (pintype "input"))
      (node (ref "IC5") (pin "11") (pinfunction "SCK_11") (pintype "input"))
      (node (ref "IC6") (pin "11") (pinfunction "SCK_11") (pintype "input"))
      (node (ref "IC7") (pin "11") (pinfunction "SCK_11") (pintype "input"))
      (node (ref "IC8") (pin "11") (pinfunction "SCK_11") (pintype "input"))
      (node (ref "JP2") (pin "3") (pinfunction "3_3") (pintype "passive"))
    )
    (net (code "13") (name "Net-(IC1A-SER)") (class "Default")
      (node (ref "IC1") (pin "14") (pinfunction "SER_14") (pintype "input"))
      (node (ref "IC2") (pin "9") (pinfunction "QH*_9") (pintype "tri_state"))
    )
    (net (code "14") (name "Net-(IC2A-QA)") (class "Default")
      (node (ref "IC2") (pin "15") (pinfunction "QA_15") (pintype "tri_state"))
      (node (ref "R15") (pin "1") (pinfunction "1_1") (pintype "passive"))
    )
    (net (code "15") (name "Net-(IC2A-QB)") (class "Default")
      (node (ref "IC2") (pin "1") (pinfunction "QB_1") (pintype "tri_state"))
      (node (ref "R16") (pin "1") (pinfunction "1_1") (pintype "passive"))
    )
    (net (code "16") (name "Net-(IC2A-QC)") (class "Default")
      (node (ref "IC2") (pin "2") (pinfunction "QC_2") (pintype "tri_state"))
      (node (ref "R17") (pin "1") (pinfunction "1_1") (pintype "passive"))
    )
    (net (code "17") (name "Net-(IC2A-QD)") (class "Default")
      (node (ref "IC2") (pin "3") (pinfunction "QD_3") (pintype "tri_state"))
      (node (ref "R18") (pin "1") (pinfunction "1_1") (pintype "passive"))
    )
    (net (code "18") (name "Net-(IC2A-QE)") (class "Default")
      (node (ref "IC2") (pin "4") (pinfunction "QE_4") (pintype "tri_state"))
      (node (ref "R19") (pin "1") (pinfunction "1_1") (pintype "passive"))
    )
    (net (code "19") (name "Net-(IC2A-QF)") (class "Default")
      (node (ref "IC2") (pin "5") (pinfunction "QF_5") (pintype "tri_state"))
      (node (ref "R20") (pin "1") (pinfunction "1_1") (pintype "passive"))
    )
    (net (code "20") (name "Net-(IC2A-QG)") (class "Default")
      (node (ref "IC2") (pin "6") (pinfunction "QG_6") (pintype "tri_state"))
      (node (ref "R21") (pin "1") (pinfunction "1_1") (pintype "passive"))
    )
    (net (code "21") (name "Net-(IC2A-QH)") (class "Default")
      (node (ref "IC2") (pin "7") (pinfunction "QH_7") (pintype "tri_state"))
      (node (ref "R22") (pin "1") (pinfunction "1_1") (pintype "passive"))
    )
    (net (code "22") (name "Net-(IC2A-SER)") (class "Default")
      (node (ref "IC2") (pin "14") (pinfunction "SER_14") (pintype "input"))
      (node (ref "IC3") (pin "9") (pinfunction "QH*_9") (pintype "tri_state"))
    )
    (net (code "23") (name "Net-(IC3A-QA)") (class "Default")
      (node (ref "IC3") (pin "15") (pinfunction "QA_15") (pintype "tri_state"))
      (node (ref "R23") (pin "1") (pinfunction "1_1") (pintype "passive"))
    )
    (net (code "24") (name "Net-(IC3A-QB)") (class "Default")
      (node (ref "IC3") (pin "1") (pinfunction "QB_1") (pintype "tri_state"))
      (node (ref "R24") (pin "1") (pinfunction "1_1") (pintype "passive"))
    )
    (net (code "25") (name "Net-(IC3A-QC)") (class "Default")
      (node (ref "IC3") (pin "2") (pinfunction "QC_2") (pintype "tri_state"))
      (node (ref "R25") (pin "1") (pinfunction "1_1") (pintype "passive"))
    )
    (net (code "26") (name "Net-(IC3A-QD)") (class "Default")
      (node (ref "IC3") (pin "3") (pinfunction "QD_3") (pintype "tri_state"))
      (node (ref "R26") (pin "1") (pinfunction "1_1") (pintype "passive"))
    )
    (net (code "27") (name "Net-(IC3A-QE)") (class "Default")
      (node (ref "IC3") (pin "4") (pinfunction "QE_4") (pintype "tri_state"))
      (node (ref "R27") (pin "1") (pinfunction "1_1") (pintype "passive"))
    )
    (net (code "28") (name "Net-(IC3A-QF)") (class "Default")
      (node (ref "IC3") (pin "5") (pinfunction "QF_5") (pintype "tri_state"))
      (node (ref "R28") (pin "1") (pinfunction "1_1") (pintype "passive"))
    )
    (net (code "29") (name "Net-(IC3A-QG)") (class "Default")
      (node (ref "IC3") (pin "6") (pinfunction "QG_6") (pintype "tri_state"))
      (node (ref "R29") (pin "1") (pinfunction "1_1") (pintype "passive"))
    )
    (net (code "30") (name "Net-(IC3A-QH)") (class "Default")
      (node (ref "IC3") (pin "7") (pinfunction "QH_7") (pintype "tri_state"))
      (node (ref "R30") (pin "1") (pinfunction "1_1") (pintype "passive"))
    )
    (net (code "31") (name "Net-(IC3A-SER)") (class "Default")
      (node (ref "IC3") (pin "14") (pinfunction "SER_14") (pintype "input"))
      (node (ref "IC4") (pin "9") (pinfunction "QH*_9") (pintype "tri_state"))
    )
    (net (code "32") (name "Net-(IC4A-QA)") (class "Default")
      (node (ref "IC4") (pin "15") (pinfunction "QA_15") (pintype "tri_state"))
      (node (ref "R31") (pin "1") (pinfunction "1_1") (pintype "passive"))
    )
    (net (code "33") (name "Net-(IC4A-QB)") (class "Default")
      (node (ref "IC4") (pin "1") (pinfunction "QB_1") (pintype "tri_state"))
      (node (ref "R32") (pin "1") (pinfunction "1_1") (pintype "passive"))
    )
    (net (code "34") (name "Net-(IC4A-QC)") (class "Default")
      (node (ref "IC4") (pin "2") (pinfunction "QC_2") (pintype "tri_state"))
      (node (ref "R33") (pin "1") (pinfunction "1_1") (pintype "passive"))
    )
    (net (code "35") (name "Net-(IC4A-QD)") (class "Default")
      (node (ref "IC4") (pin "3") (pinfunction "QD_3") (pintype "tri_state"))
      (node (ref "R34") (pin "1") (pinfunction "1_1") (pintype "passive"))
    )
    (net (code "36") (name "Net-(IC4A-QE)") (class "Default")
      (node (ref "IC4") (pin "4") (pinfunction "QE_4") (pintype "tri_state"))
      (node (ref "R35") (pin "1") (pinfunction "1_1") (pintype "passive"))
    )
    (net (code "37") (name "Net-(IC4A-QF)") (class "Default")
      (node (ref "IC4") (pin "5") (pinfunction "QF_5") (pintype "tri_state"))
      (node (ref "R36") (pin "1") (pinfunction "1_1") (pintype "passive"))
    )
    (net (code "38") (name "Net-(IC4A-QG)") (class "Default")
      (node (ref "IC4") (pin "6") (pinfunction "QG_6") (pintype "tri_state"))
      (node (ref "R37") (pin "1") (pinfunction "1_1") (pintype "passive"))
    )
    (net (code "39") (name "Net-(IC4A-QH)") (class "Default")
      (node (ref "IC4") (pin "7") (pinfunction "QH_7") (pintype "tri_state"))
      (node (ref "R38") (pin "1") (pinfunction "1_1") (pintype "passive"))
    )
    (net (code "40") (name "Net-(IC4A-SER)") (class "Default")
      (node (ref "IC4") (pin "14") (pinfunction "SER_14") (pintype "input"))
      (node (ref "IC5") (pin "9") (pinfunction "QH*_9") (pintype "tri_state"))
    )
    (net (code "41") (name "Net-(IC5A-QA)") (class "Default")
      (node (ref "IC5") (pin "15") (pinfunction "QA_15") (pintype "tri_state"))
      (node (ref "R39") (pin "1") (pinfunction "1_1") (pintype "passive"))
    )
    (net (code "42") (name "Net-(IC5A-QB)") (class "Default")
      (node (ref "IC5") (pin "1") (pinfunction "QB_1") (pintype "tri_state"))
      (node (ref "R40") (pin "1") (pinfunction "1_1") (pintype "passive"))
    )
    (net (code "43") (name "Net-(IC5A-QC)") (class "Default")
      (node (ref "IC5") (pin "2") (pinfunction "QC_2") (pintype "tri_state"))
      (node (ref "R41") (pin "1") (pinfunction "1_1") (pintype "passive"))
    )
    (net (code "44") (name "Net-(IC5A-QD)") (class "Default")
      (node (ref "IC5") (pin "3") (pinfunction "QD_3") (pintype "tri_state"))
      (node (ref "R42") (pin "1") (pinfunction "1_1") (pintype "passive"))
    )
    (net (code "45") (name "Net-(IC5A-QE)") (class "Default")
      (node (ref "IC5") (pin "4") (pinfunction "QE_4") (pintype "tri_state"))
      (node (ref "R43") (pin "1") (pinfunction "1_1") (pintype "passive"))
    )
    (net (code "46") (name "Net-(IC5A-QF)") (class "Default")
      (node (ref "IC5") (pin "5") (pinfunction "QF_5") (pintype "tri_state"))
      (node (ref "R44") (pin "1") (pinfunction "1_1") (pintype "passive"))
    )
    (net (code "47") (name "Net-(IC5A-QG)") (class "Default")
      (node (ref "IC5") (pin "6") (pinfunction "QG_6") (pintype "tri_state"))
      (node (ref "R45") (pin "1") (pinfunction "1_1") (pintype "passive"))
    )
    (net (code "48") (name "Net-(IC5A-QH)") (class "Default")
      (node (ref "IC5") (pin "7") (pinfunction "QH_7") (pintype "tri_state"))
      (node (ref "R46") (pin "1") (pinfunction "1_1") (pintype "passive"))
    )
    (net (code "49") (name "Net-(IC5A-SER)") (class "Default")
      (node (ref "IC5") (pin "14") (pinfunction "SER_14") (pintype "input"))
      (node (ref "IC6") (pin "9") (pinfunction "QH*_9") (pintype "tri_state"))
    )
    (net (code "50") (name "Net-(IC6A-QA)") (class "Default")
      (node (ref "IC6") (pin "15") (pinfunction "QA_15") (pintype "tri_state"))
      (node (ref "R47") (pin "1") (pinfunction "1_1") (pintype "passive"))
    )
    (net (code "51") (name "Net-(IC6A-QB)") (class "Default")
      (node (ref "IC6") (pin "1") (pinfunction "QB_1") (pintype "tri_state"))
      (node (ref "R48") (pin "1") (pinfunction "1_1") (pintype "passive"))
    )
    (net (code "52") (name "Net-(IC6A-QC)") (class "Default")
      (node (ref "IC6") (pin "2") (pinfunction "QC_2") (pintype "tri_state"))
      (node (ref "R49") (pin "1") (pinfunction "1_1") (pintype "passive"))
    )
    (net (code "53") (name "Net-(IC6A-QD)") (class "Default")
      (node (ref "IC6") (pin "3") (pinfunction "QD_3") (pintype "tri_state"))
      (node (ref "R50") (pin "1") (pinfunction "1_1") (pintype "passive"))
    )
    (net (code "54") (name "Net-(IC6A-QE)") (class "Default")
      (node (ref "IC6") (pin "4") (pinfunction "QE_4") (pintype "tri_state"))
      (node (ref "R51") (pin "1") (pinfunction "1_1") (pintype "passive"))
    )
    (net (code "55") (name "Net-(IC6A-QF)") (class "Default")
      (node (ref "IC6") (pin "5") (pinfunction "QF_5") (pintype "tri_state"))
      (node (ref "R52") (pin "1") (pinfunction "1_1") (pintype "passive"))
    )
    (net (code "56") (name "Net-(IC6A-QG)") (class "Default")
      (node (ref "IC6") (pin "6") (pinfunction "QG_6") (pintype "tri_state"))
      (node (ref "R53") (pin "1") (pinfunction "1_1") (pintype "passive"))
    )
    (net (code "57") (name "Net-(IC6A-QH)") (class "Default")
      (node (ref "IC6") (pin "7") (pinfunction "QH_7") (pintype "tri_state"))
      (node (ref "R54") (pin "1") (pinfunction "1_1") (pintype "passive"))
    )
    (net (code "58") (name "Net-(IC6A-SER)") (class "Default")
      (node (ref "IC6") (pin "14") (pinfunction "SER_14") (pintype "input"))
      (node (ref "IC7") (pin "9") (pinfunction "QH*_9") (pintype "tri_state"))
    )
    (net (code "59") (name "Net-(IC7A-QA)") (class "Default")
      (node (ref "IC7") (pin "15") (pinfunction "QA_15") (pintype "tri_state"))
      (node (ref "R55") (pin "1") (pinfunction "1_1") (pintype "passive"))
    )
    (net (code "60") (name "Net-(IC7A-QB)") (class "Default")
      (node (ref "IC7") (pin "1") (pinfunction "QB_1") (pintype "tri_state"))
      (node (ref "R56") (pin "1") (pinfunction "1_1") (pintype "passive"))
    )
    (net (code "61") (name "Net-(IC7A-QC)") (class "Default")
      (node (ref "IC7") (pin "2") (pinfunction "QC_2") (pintype "tri_state"))
      (node (ref "R57") (pin "1") (pinfunction "1_1") (pintype "passive"))
    )
    (net (code "62") (name "Net-(IC7A-QD)") (class "Default")
      (node (ref "IC7") (pin "3") (pinfunction "QD_3") (pintype "tri_state"))
      (node (ref "R58") (pin "1") (pinfunction "1_1") (pintype "passive"))
    )
    (net (code "63") (name "Net-(IC7A-QE)") (class "Default")
      (node (ref "IC7") (pin "4") (pinfunction "QE_4") (pintype "tri_state"))
      (node (ref "R59") (pin "1") (pinfunction "1_1") (pintype "passive"))
    )
    (net (code "64") (name "Net-(IC7A-QF)") (class "Default")
      (node (ref "IC7") (pin "5") (pinfunction "QF_5") (pintype "tri_state"))
      (node (ref "R60") (pin "1") (pinfunction "1_1") (pintype "passive"))
    )
    (net (code "65") (name "Net-(IC7A-QG)") (class "Default")
      (node (ref "IC7") (pin "6") (pinfunction "QG_6") (pintype "tri_state"))
      (node (ref "R61") (pin "1") (pinfunction "1_1") (pintype "passive"))
    )
    (net (code "66") (name "Net-(IC7A-QH)") (class "Default")
      (node (ref "IC7") (pin "7") (pinfunction "QH_7") (pintype "tri_state"))
      (node (ref "R62") (pin "1") (pinfunction "1_1") (pintype "passive"))
    )
    (net (code "67") (name "Net-(IC7A-SER)") (class "Default")
      (node (ref "IC7") (pin "14") (pinfunction "SER_14") (pintype "input"))
      (node (ref "IC8") (pin "9") (pinfunction "QH*_9") (pintype "tri_state"))
    )
    (net (code "68") (name "Net-(IC8A-QA)") (class "Default")
      (node (ref "IC8") (pin "15") (pinfunction "QA_15") (pintype "tri_state"))
      (node (ref "R63") (pin "1") (pinfunction "1_1") (pintype "passive"))
    )
    (net (code "69") (name "Net-(IC8A-QB)") (class "Default")
      (node (ref "IC8") (pin "1") (pinfunction "QB_1") (pintype "tri_state"))
      (node (ref "R64") (pin "1") (pinfunction "1_1") (pintype "passive"))
    )
    (net (code "70") (name "Net-(IC8A-QC)") (class "Default")
      (node (ref "IC8") (pin "2") (pinfunction "QC_2") (pintype "tri_state"))
      (node (ref "R65") (pin "1") (pinfunction "1_1") (pintype "passive"))
    )
    (net (code "71") (name "Net-(IC8A-QD)") (class "Default")
      (node (ref "IC8") (pin "3") (pinfunction "QD_3") (pintype "tri_state"))
      (node (ref "R66") (pin "1") (pinfunction "1_1") (pintype "passive"))
    )
    (net (code "72") (name "Net-(IC8A-QE)") (class "Default")
      (node (ref "IC8") (pin "4") (pinfunction "QE_4") (pintype "tri_state"))
      (node (ref "R67") (pin "1") (pinfunction "1_1") (pintype "passive"))
    )
    (net (code "73") (name "Net-(IC8A-QF)") (class "Default")
      (node (ref "IC8") (pin "5") (pinfunction "QF_5") (pintype "tri_state"))
      (node (ref "R68") (pin "1") (pinfunction "1_1") (pintype "passive"))
    )
    (net (code "74") (name "Net-(IC8A-QG)") (class "Default")
      (node (ref "IC8") (pin "6") (pinfunction "QG_6") (pintype "tri_state"))
      (node (ref "R69") (pin "1") (pinfunction "1_1") (pintype "passive"))
    )
    (net (code "75") (name "Net-(IC8A-QH)") (class "Default")
      (node (ref "IC8") (pin "7") (pinfunction "QH_7") (pintype "tri_state"))
      (node (ref "R70") (pin "1") (pinfunction "1_1") (pintype "passive"))
    )
    (net (code "76") (name "Net-(IC8A-SER)") (class "Default")
      (node (ref "IC8") (pin "14") (pinfunction "SER_14") (pintype "input"))
      (node (ref "JP2") (pin "2") (pinfunction "2_2") (pintype "passive"))
    )
    (net (code "77") (name "Net-(Q1-B)") (class "Default")
      (node (ref "Q1") (pin "1") (pinfunction "B_1") (pintype "passive"))
      (node (ref "R7") (pin "2") (pinfunction "2_2") (pintype "passive"))
    )
    (net (code "78") (name "Net-(Q1-C)") (class "Default")
      (node (ref "N1") (pin "D8") (pinfunction "D8_D8") (pintype "bidirectional"))
      (node (ref "Q1") (pin "3") (pinfunction "C_3") (pintype "passive"))
    )
    (net (code "79") (name "Net-(Q2-B)") (class "Default")
      (node (ref "Q2") (pin "1") (pinfunction "B_1") (pintype "passive"))
      (node (ref "R8") (pin "2") (pinfunction "2_2") (pintype "passive"))
    )
    (net (code "80") (name "Net-(Q2-C)") (class "Default")
      (node (ref "N1") (pin "D9") (pinfunction "D9_D9") (pintype "bidirectional"))
      (node (ref "Q2") (pin "3") (pinfunction "C_3") (pintype "passive"))
    )
    (net (code "81") (name "Net-(Q3-B)") (class "Default")
      (node (ref "Q3") (pin "1") (pinfunction "B_1") (pintype "passive"))
      (node (ref "R9") (pin "2") (pinfunction "2_2") (pintype "passive"))
    )
    (net (code "82") (name "Net-(Q3-C)") (class "Default")
      (node (ref "N1") (pin "D0") (pinfunction "D0_D0") (pintype "bidirectional"))
      (node (ref "Q3") (pin "3") (pinfunction "C_3") (pintype "passive"))
    )
    (net (code "83") (name "Net-(Q4-B)") (class "Default")
      (node (ref "Q4") (pin "1") (pinfunction "B_1") (pintype "passive"))
      (node (ref "R10") (pin "2") (pinfunction "2_2") (pintype "passive"))
    )
    (net (code "84") (name "Net-(Q4-C)") (class "Default")
      (node (ref "N1") (pin "D1") (pinfunction "D1_D1") (pintype "bidirectional"))
      (node (ref "Q4") (pin "3") (pinfunction "C_3") (pintype "passive"))
    )
    (net (code "85") (name "Net-(Q5-B)") (class "Default")
      (node (ref "Q5") (pin "1") (pinfunction "B_1") (pintype "passive"))
      (node (ref "R11") (pin "2") (pinfunction "2_2") (pintype "passive"))
    )
    (net (code "86") (name "Net-(Q5-C)") (class "Default")
      (node (ref "N1") (pin "D2") (pinfunction "D2_D2") (pintype "bidirectional"))
      (node (ref "Q5") (pin "3") (pinfunction "C_3") (pintype "passive"))
    )
    (net (code "87") (name "Net-(Q6-B)") (class "Default")
      (node (ref "Q6") (pin "1") (pinfunction "B_1") (pintype "passive"))
      (node (ref "R12") (pin "2") (pinfunction "2_2") (pintype "passive"))
    )
    (net (code "88") (name "Net-(Q6-C)") (class "Default")
      (node (ref "N1") (pin "D3") (pinfunction "D3_D3") (pintype "bidirectional"))
      (node (ref "Q6") (pin "3") (pinfunction "C_3") (pintype "passive"))
    )
    (net (code "89") (name "Net-(Q7-B)") (class "Default")
      (node (ref "Q7") (pin "1") (pinfunction "B_1") (pintype "passive"))
      (node (ref "R13") (pin "2") (pinfunction "2_2") (pintype "passive"))
    )
    (net (code "90") (name "Net-(Q7-C)") (class "Default")
      (node (ref "N1") (pin "D4") (pinfunction "D4_D4") (pintype "bidirectional"))
      (node (ref "Q7") (pin "3") (pinfunction "C_3") (pintype "passive"))
    )
    (net (code "91") (name "Net-(Q8-B)") (class "Default")
      (node (ref "Q8") (pin "1") (pinfunction "B_1") (pintype "passive"))
      (node (ref "R14") (pin "2") (pinfunction "2_2") (pintype "passive"))
    )
    (net (code "92") (name "Net-(Q8-C)") (class "Default")
      (node (ref "N1") (pin "D5") (pinfunction "D5_D5") (pintype "bidirectional"))
      (node (ref "Q8") (pin "3") (pinfunction "C_3") (pintype "passive"))
    )
    (net (code "93") (name "Net-(Q9-B)") (class "Default")
      (node (ref "Q9") (pin "1") (pinfunction "B_1") (pintype "passive"))
      (node (ref "R15") (pin "2") (pinfunction "2_2") (pintype "passive"))
    )
    (net (code "94") (name "Net-(Q9-C)") (class "Default")
      (node (ref "N2") (pin "D0") (pinfunction "D0_D0") (pintype "bidirectional"))
      (node (ref "Q9") (pin "3") (pinfunction "C_3") (pintype "passive"))
    )
    (net (code "95") (name "Net-(Q10-B)") (class "Default")
      (node (ref "Q10") (pin "1") (pinfunction "B_1") (pintype "passive"))
      (node (ref "R16") (pin "2") (pinfunction "2_2") (pintype "passive"))
    )
    (net (code "96") (name "Net-(Q10-C)") (class "Default")
      (node (ref "N2") (pin "D1") (pinfunction "D1_D1") (pintype "bidirectional"))
      (node (ref "Q10") (pin "3") (pinfunction "C_3") (pintype "passive"))
    )
    (net (code "97") (name "Net-(Q11-B)") (class "Default")
      (node (ref "Q11") (pin "1") (pinfunction "B_1") (pintype "passive"))
      (node (ref "R17") (pin "2") (pinfunction "2_2") (pintype "passive"))
    )
    (net (code "98") (name "Net-(Q11-C)") (class "Default")
      (node (ref "N2") (pin "D2") (pinfunction "D2_D2") (pintype "bidirectional"))
      (node (ref "Q11") (pin "3") (pinfunction "C_3") (pintype "passive"))
    )
    (net (code "99") (name "Net-(Q12-B)") (class "Default")
      (node (ref "Q12") (pin "1") (pinfunction "B_1") (pintype "passive"))
      (node (ref "R18") (pin "2") (pinfunction "2_2") (pintype "passive"))
    )
    (net (code "100") (name "Net-(Q12-C)") (class "Default")
      (node (ref "N2") (pin "D3") (pinfunction "D3_D3") (pintype "bidirectional"))
      (node (ref "Q12") (pin "3") (pinfunction "C_3") (pintype "passive"))
    )
    (net (code "101") (name "Net-(Q13-B)") (class "Default")
      (node (ref "Q13") (pin "1") (pinfunction "B_1") (pintype "passive"))
      (node (ref "R19") (pin "2") (pinfunction "2_2") (pintype "passive"))
    )
    (net (code "102") (name "Net-(Q13-C)") (class "Default")
      (node (ref "N2") (pin "D4") (pinfunction "D4_D4") (pintype "bidirectional"))
      (node (ref "Q13") (pin "3") (pinfunction "C_3") (pintype "passive"))
    )
    (net (code "103") (name "Net-(Q14-B)") (class "Default")
      (node (ref "Q14") (pin "1") (pinfunction "B_1") (pintype "passive"))
      (node (ref "R20") (pin "2") (pinfunction "2_2") (pintype "passive"))
    )
    (net (code "104") (name "Net-(Q14-C)") (class "Default")
      (node (ref "N2") (pin "D5") (pinfunction "D5_D5") (pintype "bidirectional"))
      (node (ref "Q14") (pin "3") (pinfunction "C_3") (pintype "passive"))
    )
    (net (code "105") (name "Net-(Q15-B)") (class "Default")
      (node (ref "Q15") (pin "1") (pinfunction "B_1") (pintype "passive"))
      (node (ref "R21") (pin "2") (pinfunction "2_2") (pintype "passive"))
    )
    (net (code "106") (name "Net-(Q15-C)") (class "Default")
      (node (ref "N1") (pin "D6") (pinfunction "D6_D6") (pintype "bidirectional"))
      (node (ref "Q15") (pin "3") (pinfunction "C_3") (pintype "passive"))
    )
    (net (code "107") (name "Net-(Q16-B)") (class "Default")
      (node (ref "Q16") (pin "1") (pinfunction "B_1") (pintype "passive"))
      (node (ref "R22") (pin "2") (pinfunction "2_2") (pintype "passive"))
    )
    (net (code "108") (name "Net-(Q16-C)") (class "Default")
      (node (ref "N1") (pin "D7") (pinfunction "D7_D7") (pintype "bidirectional"))
      (node (ref "Q16") (pin "3") (pinfunction "C_3") (pintype "passive"))
    )
    (net (code "109") (name "Net-(Q17-B)") (class "Default")
      (node (ref "Q17") (pin "1") (pinfunction "B_1") (pintype "passive"))
      (node (ref "R23") (pin "2") (pinfunction "2_2") (pintype "passive"))
    )
    (net (code "110") (name "Net-(Q17-C)") (class "Default")
      (node (ref "N3") (pin "D4") (pinfunction "D4_D4") (pintype "bidirectional"))
      (node (ref "Q17") (pin "3") (pinfunction "C_3") (pintype "passive"))
    )
    (net (code "111") (name "Net-(Q18-B)") (class "Default")
      (node (ref "Q18") (pin "1") (pinfunction "B_1") (pintype "passive"))
      (node (ref "R24") (pin "2") (pinfunction "2_2") (pintype "passive"))
    )
    (net (code "112") (name "Net-(Q18-C)") (class "Default")
      (node (ref "N3") (pin "D5") (pinfunction "D5_D5") (pintype "bidirectional"))
      (node (ref "Q18") (pin "3") (pinfunction "C_3") (pintype "passive"))
    )
    (net (code "113") (name "Net-(Q19-B)") (class "Default")
      (node (ref "Q19") (pin "1") (pinfunction "B_1") (pintype "passive"))
      (node (ref "R25") (pin "2") (pinfunction "2_2") (pintype "passive"))
    )
    (net (code "114") (name "Net-(Q20-B)") (class "Default")
      (node (ref "Q20") (pin "1") (pinfunction "B_1") (pintype "passive"))
      (node (ref "R26") (pin "2") (pinfunction "2_2") (pintype "passive"))
    )
    (net (code "115") (name "Net-(Q21-B)") (class "Default")
      (node (ref "Q21") (pin "1") (pinfunction "B_1") (pintype "passive"))
      (node (ref "R27") (pin "2") (pinfunction "2_2") (pintype "passive"))
    )
    (net (code "116") (name "Net-(Q21-C)") (class "Default")
      (node (ref "N2") (pin "D6") (pinfunction "D6_D6") (pintype "bidirectional"))
      (node (ref "Q21") (pin "3") (pinfunction "C_3") (pintype "passive"))
    )
    (net (code "117") (name "Net-(Q22-B)") (class "Default")
      (node (ref "Q22") (pin "1") (pinfunction "B_1") (pintype "passive"))
      (node (ref "R28") (pin "2") (pinfunction "2_2") (pintype "passive"))
    )
    (net (code "118") (name "Net-(Q22-C)") (class "Default")
      (node (ref "N2") (pin "D7") (pinfunction "D7_D7") (pintype "bidirectional"))
      (node (ref "Q22") (pin "3") (pinfunction "C_3") (pintype "passive"))
    )
    (net (code "119") (name "Net-(Q23-B)") (class "Default")
      (node (ref "Q23") (pin "1") (pinfunction "B_1") (pintype "passive"))
      (node (ref "R29") (pin "2") (pinfunction "2_2") (pintype "passive"))
    )
    (net (code "120") (name "Net-(Q23-C)") (class "Default")
      (node (ref "N2") (pin "D8") (pinfunction "D8_D8") (pintype "bidirectional"))
      (node (ref "Q23") (pin "3") (pinfunction "C_3") (pintype "passive"))
    )
    (net (code "121") (name "Net-(Q24-B)") (class "Default")
      (node (ref "Q24") (pin "1") (pinfunction "B_1") (pintype "passive"))
      (node (ref "R30") (pin "2") (pinfunction "2_2") (pintype "passive"))
    )
    (net (code "122") (name "Net-(Q24-C)") (class "Default")
      (node (ref "N2") (pin "D9") (pinfunction "D9_D9") (pintype "bidirectional"))
      (node (ref "Q24") (pin "3") (pinfunction "C_3") (pintype "passive"))
    )
    (net (code "123") (name "Net-(Q25-B)") (class "Default")
      (node (ref "Q25") (pin "1") (pinfunction "B_1") (pintype "passive"))
      (node (ref "R31") (pin "2") (pinfunction "2_2") (pintype "passive"))
    )
    (net (code "124") (name "Net-(Q25-C)") (class "Default")
      (node (ref "N3") (pin "D6") (pinfunction "D6_D6") (pintype "bidirectional"))
      (node (ref "Q25") (pin "3") (pinfunction "C_3") (pintype "passive"))
    )
    (net (code "125") (name "Net-(Q26-B)") (class "Default")
      (node (ref "Q26") (pin "1") (pinfunction "B_1") (pintype "passive"))
      (node (ref "R32") (pin "2") (pinfunction "2_2") (pintype "passive"))
    )
    (net (code "126") (name "Net-(Q26-C)") (class "Default")
      (node (ref "N3") (pin "D7") (pinfunction "D7_D7") (pintype "bidirectional"))
      (node (ref "Q26") (pin "3") (pinfunction "C_3") (pintype "passive"))
    )
    (net (code "127") (name "Net-(Q27-B)") (class "Default")
      (node (ref "Q27") (pin "1") (pinfunction "B_1") (pintype "passive"))
      (node (ref "R33") (pin "2") (pinfunction "2_2") (pintype "passive"))
    )
    (net (code "128") (name "Net-(Q27-C)") (class "Default")
      (node (ref "N3") (pin "D8") (pinfunction "D8_D8") (pintype "bidirectional"))
      (node (ref "Q27") (pin "3") (pinfunction "C_3") (pintype "passive"))
    )
    (net (code "129") (name "Net-(Q28-B)") (class "Default")
      (node (ref "Q28") (pin "1") (pinfunction "B_1") (pintype "passive"))
      (node (ref "R34") (pin "2") (pinfunction "2_2") (pintype "passive"))
    )
    (net (code "130") (name "Net-(Q28-C)") (class "Default")
      (node (ref "N3") (pin "D9") (pinfunction "D9_D9") (pintype "bidirectional"))
      (node (ref "Q28") (pin "3") (pinfunction "C_3") (pintype "passive"))
    )
    (net (code "131") (name "Net-(Q29-B)") (class "Default")
      (node (ref "Q29") (pin "1") (pinfunction "B_1") (pintype "passive"))
      (node (ref "R35") (pin "2") (pinfunction "2_2") (pintype "passive"))
    )
    (net (code "132") (name "Net-(Q29-C)") (class "Default")
      (node (ref "N3") (pin "D0") (pinfunction "D0_D0") (pintype "bidirectional"))
      (node (ref "Q29") (pin "3") (pinfunction "C_3") (pintype "passive"))
    )
    (net (code "133") (name "Net-(Q30-B)") (class "Default")
      (node (ref "Q30") (pin "1") (pinfunction "B_1") (pintype "passive"))
      (node (ref "R36") (pin "2") (pinfunction "2_2") (pintype "passive"))
    )
    (net (code "134") (name "Net-(Q30-C)") (class "Default")
      (node (ref "N3") (pin "D1") (pinfunction "D1_D1") (pintype "bidirectional"))
      (node (ref "Q30") (pin "3") (pinfunction "C_3") (pintype "passive"))
    )
    (net (code "135") (name "Net-(Q31-B)") (class "Default")
      (node (ref "Q31") (pin "1") (pinfunction "B_1") (pintype "passive"))
      (node (ref "R37") (pin "2") (pinfunction "2_2") (pintype "passive"))
    )
    (net (code "136") (name "Net-(Q31-C)") (class "Default")
      (node (ref "N3") (pin "D2") (pinfunction "D2_D2") (pintype "bidirectional"))
      (node (ref "Q31") (pin "3") (pinfunction "C_3") (pintype "passive"))
    )
    (net (code "137") (name "Net-(Q32-B)") (class "Default")
      (node (ref "Q32") (pin "1") (pinfunction "B_1") (pintype "passive"))
      (node (ref "R38") (pin "2") (pinfunction "2_2") (pintype "passive"))
    )
    (net (code "138") (name "Net-(Q32-C)") (class "Default")
      (node (ref "N3") (pin "D3") (pinfunction "D3_D3") (pintype "bidirectional"))
      (node (ref "Q32") (pin "3") (pinfunction "C_3") (pintype "passive"))
    )
    (net (code "139") (name "Net-(Q33-B)") (class "Default")
      (node (ref "Q33") (pin "1") (pinfunction "B_1") (pintype "passive"))
      (node (ref "R39") (pin "2") (pinfunction "2_2") (pintype "passive"))
    )
    (net (code "140") (name "Net-(Q33-C)") (class "Default")
      (node (ref "N4") (pin "D8") (pinfunction "D8_D8") (pintype "bidirectional"))
      (node (ref "Q33") (pin "3") (pinfunction "C_3") (pintype "passive"))
    )
    (net (code "141") (name "Net-(Q34-B)") (class "Default")
      (node (ref "Q34") (pin "1") (pinfunction "B_1") (pintype "passive"))
      (node (ref "R40") (pin "2") (pinfunction "2_2") (pintype "passive"))
    )
    (net (code "142") (name "Net-(Q34-C)") (class "Default")
      (node (ref "N4") (pin "D9") (pinfunction "D9_D9") (pintype "bidirectional"))
      (node (ref "Q34") (pin "3") (pinfunction "C_3") (pintype "passive"))
    )
    (net (code "143") (name "Net-(Q35-B)") (class "Default")
      (node (ref "Q35") (pin "1") (pinfunction "B_1") (pintype "passive"))
      (node (ref "R41") (pin "2") (pinfunction "2_2") (pintype "passive"))
    )
    (net (code "144") (name "Net-(Q35-C)") (class "Default")
      (node (ref "N4") (pin "D0") (pinfunction "D0_D0") (pintype "bidirectional"))
      (node (ref "Q35") (pin "3") (pinfunction "C_3") (pintype "passive"))
    )
    (net (code "145") (name "Net-(Q36-B)") (class "Default")
      (node (ref "Q36") (pin "1") (pinfunction "B_1") (pintype "passive"))
      (node (ref "R42") (pin "2") (pinfunction "2_2") (pintype "passive"))
    )
    (net (code "146") (name "Net-(Q36-C)") (class "Default")
      (node (ref "N4") (pin "D1") (pinfunction "D1_D1") (pintype "bidirectional"))
      (node (ref "Q36") (pin "3") (pinfunction "C_3") (pintype "passive"))
    )
    (net (code "147") (name "Net-(Q37-B)") (class "Default")
      (node (ref "Q37") (pin "1") (pinfunction "B_1") (pintype "passive"))
      (node (ref "R43") (pin "2") (pinfunction "2_2") (pintype "passive"))
    )
    (net (code "148") (name "Net-(Q37-C)") (class "Default")
      (node (ref "N4") (pin "D2") (pinfunction "D2_D2") (pintype "bidirectional"))
      (node (ref "Q37") (pin "3") (pinfunction "C_3") (pintype "passive"))
    )
    (net (code "149") (name "Net-(Q38-B)") (class "Default")
      (node (ref "Q38") (pin "1") (pinfunction "B_1") (pintype "passive"))
      (node (ref "R44") (pin "2") (pinfunction "2_2") (pintype "passive"))
    )
    (net (code "150") (name "Net-(Q38-C)") (class "Default")
      (node (ref "N4") (pin "D3") (pinfunction "D3_D3") (pintype "bidirectional"))
      (node (ref "Q38") (pin "3") (pinfunction "C_3") (pintype "passive"))
    )
    (net (code "151") (name "Net-(Q39-B)") (class "Default")
      (node (ref "Q39") (pin "1") (pinfunction "B_1") (pintype "passive"))
      (node (ref "R45") (pin "2") (pinfunction "2_2") (pintype "passive"))
    )
    (net (code "152") (name "Net-(Q39-C)") (class "Default")
      (node (ref "N4") (pin "D4") (pinfunction "D4_D4") (pintype "bidirectional"))
      (node (ref "Q39") (pin "3") (pinfunction "C_3") (pintype "passive"))
    )
    (net (code "153") (name "Net-(Q40-B)") (class "Default")
      (node (ref "Q40") (pin "1") (pinfunction "B_1") (pintype "passive"))
      (node (ref "R46") (pin "2") (pinfunction "2_2") (pintype "passive"))
    )
    (net (code "154") (name "Net-(Q40-C)") (class "Default")
      (node (ref "N4") (pin "D5") (pinfunction "D5_D5") (pintype "bidirectional"))
      (node (ref "Q40") (pin "3") (pinfunction "C_3") (pintype "passive"))
    )
    (net (code "155") (name "Net-(Q41-B)") (class "Default")
      (node (ref "Q41") (pin "1") (pinfunction "B_1") (pintype "passive"))
      (node (ref "R47") (pin "2") (pinfunction "2_2") (pintype "passive"))
    )
    (net (code "156") (name "Net-(Q41-C)") (class "Default")
      (node (ref "N5") (pin "D2") (pinfunction "D2_D2") (pintype "bidirectional"))
      (node (ref "Q41") (pin "3") (pinfunction "C_3") (pintype "passive"))
    )
    (net (code "157") (name "Net-(Q42-B)") (class "Default")
      (node (ref "Q42") (pin "1") (pinfunction "B_1") (pintype "passive"))
      (node (ref "R48") (pin "2") (pinfunction "2_2") (pintype "passive"))
    )
    (net (code "158") (name "Net-(Q42-C)") (class "Default")
      (node (ref "N5") (pin "D3") (pinfunction "D3_D3") (pintype "bidirectional"))
      (node (ref "Q42") (pin "3") (pinfunction "C_3") (pintype "passive"))
    )
    (net (code "159") (name "Net-(Q43-B)") (class "Default")
      (node (ref "Q43") (pin "1") (pinfunction "B_1") (pintype "passive"))
      (node (ref "R49") (pin "2") (pinfunction "2_2") (pintype "passive"))
    )
    (net (code "160") (name "Net-(Q43-C)") (class "Default")
      (node (ref "N5") (pin "D4") (pinfunction "D4_D4") (pintype "bidirectional"))
      (node (ref "Q43") (pin "3") (pinfunction "C_3") (pintype "passive"))
    )
    (net (code "161") (name "Net-(Q44-B)") (class "Default")
      (node (ref "Q44") (pin "1") (pinfunction "B_1") (pintype "passive"))
      (node (ref "R50") (pin "2") (pinfunction "2_2") (pintype "passive"))
    )
    (net (code "162") (name "Net-(Q44-C)") (class "Default")
      (node (ref "N5") (pin "D5") (pinfunction "D5_D5") (pintype "bidirectional"))
      (node (ref "Q44") (pin "3") (pinfunction "C_3") (pintype "passive"))
    )
    (net (code "163") (name "Net-(Q45-B)") (class "Default")
      (node (ref "Q45") (pin "1") (pinfunction "B_1") (pintype "passive"))
      (node (ref "R51") (pin "2") (pinfunction "2_2") (pintype "passive"))
    )
    (net (code "164") (name "Net-(Q46-B)") (class "Default")
      (node (ref "Q46") (pin "1") (pinfunction "B_1") (pintype "passive"))
      (node (ref "R52") (pin "2") (pinfunction "2_2") (pintype "passive"))
    )
    (net (code "165") (name "Net-(Q47-B)") (class "Default")
      (node (ref "Q47") (pin "1") (pinfunction "B_1") (pintype "passive"))
      (node (ref "R53") (pin "2") (pinfunction "2_2") (pintype "passive"))
    )
    (net (code "166") (name "Net-(Q47-C)") (class "Default")
      (node (ref "N4") (pin "D6") (pinfunction "D6_D6") (pintype "bidirectional"))
      (node (ref "Q47") (pin "3") (pinfunction "C_3") (pintype "passive"))
    )
    (net (code "167") (name "Net-(Q48-B)") (class "Default")
      (node (ref "Q48") (pin "1") (pinfunction "B_1") (pintype "passive"))
      (node (ref "R54") (pin "2") (pinfunction "2_2") (pintype "passive"))
    )
    (net (code "168") (name "Net-(Q48-C)") (class "Default")
      (node (ref "N4") (pin "D7") (pinfunction "D7_D7") (pintype "bidirectional"))
      (node (ref "Q48") (pin "3") (pinfunction "C_3") (pintype "passive"))
    )
    (net (code "169") (name "Net-(Q49-B)") (class "Default")
      (node (ref "Q49") (pin "1") (pinfunction "B_1") (pintype "passive"))
      (node (ref "R55") (pin "2") (pinfunction "2_2") (pintype "passive"))
    )
    (net (code "170") (name "Net-(Q49-C)") (class "Default")
      (node (ref "N6") (pin "D4") (pinfunction "D4_D4") (pintype "bidirectional"))
      (node (ref "Q49") (pin "3") (pinfunction "C_3") (pintype "passive"))
    )
    (net (code "171") (name "Net-(Q50-B)") (class "Default")
      (node (ref "Q50") (pin "1") (pinfunction "B_1") (pintype "passive"))
      (node (ref "R56") (pin "2") (pinfunction "2_2") (pintype "passive"))
    )
    (net (code "172") (name "Net-(Q50-C)") (class "Default")
      (node (ref "N6") (pin "D5") (pinfunction "D5_D5") (pintype "bidirectional"))
      (node (ref "Q50") (pin "3") (pinfunction "C_3") (pintype "passive"))
    )
    (net (code "173") (name "Net-(Q51-B)") (class "Default")
      (node (ref "Q51") (pin "1") (pinfunction "B_1") (pintype "passive"))
      (node (ref "R57") (pin "2") (pinfunction "2_2") (pintype "passive"))
    )
    (net (code "174") (name "Net-(Q51-C)") (class "Default")
      (node (ref "N5") (pin "D6") (pinfunction "D6_D6") (pintype "bidirectional"))
      (node (ref "Q51") (pin "3") (pinfunction "C_3") (pintype "passive"))
    )
    (net (code "175") (name "Net-(Q52-B)") (class "Default")
      (node (ref "Q52") (pin "1") (pinfunction "B_1") (pintype "passive"))
      (node (ref "R58") (pin "2") (pinfunction "2_2") (pintype "passive"))
    )
    (net (code "176") (name "Net-(Q52-C)") (class "Default")
      (node (ref "N5") (pin "D7") (pinfunction "D7_D7") (pintype "bidirectional"))
      (node (ref "Q52") (pin "3") (pinfunction "C_3") (pintype "passive"))
    )
    (net (code "177") (name "Net-(Q53-B)") (class "Default")
      (node (ref "Q53") (pin "1") (pinfunction "B_1") (pintype "passive"))
      (node (ref "R59") (pin "2") (pinfunction "2_2") (pintype "passive"))
    )
    (net (code "178") (name "Net-(Q53-C)") (class "Default")
      (node (ref "N5") (pin "D8") (pinfunction "D8_D8") (pintype "bidirectional"))
      (node (ref "Q53") (pin "3") (pinfunction "C_3") (pintype "passive"))
    )
    (net (code "179") (name "Net-(Q54-B)") (class "Default")
      (node (ref "Q54") (pin "1") (pinfunction "B_1") (pintype "passive"))
      (node (ref "R60") (pin "2") (pinfunction "2_2") (pintype "passive"))
    )
    (net (code "180") (name "Net-(Q54-C)") (class "Default")
      (node (ref "N5") (pin "D9") (pinfunction "D9_D9") (pintype "bidirectional"))
      (node (ref "Q54") (pin "3") (pinfunction "C_3") (pintype "passive"))
    )
    (net (code "181") (name "Net-(Q55-B)") (class "Default")
      (node (ref "Q55") (pin "1") (pinfunction "B_1") (pintype "passive"))
      (node (ref "R61") (pin "2") (pinfunction "2_2") (pintype "passive"))
    )
    (net (code "182") (name "Net-(Q55-C)") (class "Default")
      (node (ref "N5") (pin "D0") (pinfunction "D0_D0") (pintype "bidirectional"))
      (node (ref "Q55") (pin "3") (pinfunction "C_3") (pintype "passive"))
    )
    (net (code "183") (name "Net-(Q56-B)") (class "Default")
      (node (ref "Q56") (pin "1") (pinfunction "B_1") (pintype "passive"))
      (node (ref "R62") (pin "2") (pinfunction "2_2") (pintype "passive"))
    )
    (net (code "184") (name "Net-(Q56-C)") (class "Default")
      (node (ref "N5") (pin "D1") (pinfunction "D1_D1") (pintype "bidirectional"))
      (node (ref "Q56") (pin "3") (pinfunction "C_3") (pintype "passive"))
    )
    (net (code "185") (name "Net-(Q57-B)") (class "Default")
      (node (ref "Q57") (pin "1") (pinfunction "B_1") (pintype "passive"))
      (node (ref "R63") (pin "2") (pinfunction "2_2") (pintype "passive"))
    )
    (net (code "186") (name "Net-(Q57-C)") (class "Default")
      (node (ref "N6") (pin "D6") (pinfunction "D6_D6") (pintype "bidirectional"))
      (node (ref "Q57") (pin "3") (pinfunction "C_3") (pintype "passive"))
    )
    (net (code "187") (name "Net-(Q58-B)") (class "Default")
      (node (ref "Q58") (pin "1") (pinfunction "B_1") (pintype "passive"))
      (node (ref "R64") (pin "2") (pinfunction "2_2") (pintype "passive"))
    )
    (net (code "188") (name "Net-(Q58-C)") (class "Default")
      (node (ref "N6") (pin "D7") (pinfunction "D7_D7") (pintype "bidirectional"))
      (node (ref "Q58") (pin "3") (pinfunction "C_3") (pintype "passive"))
    )
    (net (code "189") (name "Net-(Q59-B)") (class "Default")
      (node (ref "Q59") (pin "1") (pinfunction "B_1") (pintype "passive"))
      (node (ref "R65") (pin "2") (pinfunction "2_2") (pintype "passive"))
    )
    (net (code "190") (name "Net-(Q59-C)") (class "Default")
      (node (ref "N6") (pin "D8") (pinfunction "D8_D8") (pintype "bidirectional"))
      (node (ref "Q59") (pin "3") (pinfunction "C_3") (pintype "passive"))
    )
    (net (code "191") (name "Net-(Q60-B)") (class "Default")
      (node (ref "Q60") (pin "1") (pinfunction "B_1") (pintype "passive"))
      (node (ref "R66") (pin "2") (pinfunction "2_2") (pintype "passive"))
    )
    (net (code "192") (name "Net-(Q60-C)") (class "Default")
      (node (ref "N6") (pin "D9") (pinfunction "D9_D9") (pintype "bidirectional"))
      (node (ref "Q60") (pin "3") (pinfunction "C_3") (pintype "passive"))
    )
    (net (code "193") (name "Net-(Q61-B)") (class "Default")
      (node (ref "Q61") (pin "1") (pinfunction "B_1") (pintype "passive"))
      (node (ref "R67") (pin "2") (pinfunction "2_2") (pintype "passive"))
    )
    (net (code "194") (name "Net-(Q61-C)") (class "Default")
      (node (ref "N6") (pin "D0") (pinfunction "D0_D0") (pintype "bidirectional"))
      (node (ref "Q61") (pin "3") (pinfunction "C_3") (pintype "passive"))
    )
    (net (code "195") (name "Net-(Q62-B)") (class "Default")
      (node (ref "Q62") (pin "1") (pinfunction "B_1") (pintype "passive"))
      (node (ref "R68") (pin "2") (pinfunction "2_2") (pintype "passive"))
    )
    (net (code "196") (name "Net-(Q62-C)") (class "Default")
      (node (ref "N6") (pin "D1") (pinfunction "D1_D1") (pintype "bidirectional"))
      (node (ref "Q62") (pin "3") (pinfunction "C_3") (pintype "passive"))
    )
    (net (code "197") (name "Net-(Q63-B)") (class "Default")
      (node (ref "Q63") (pin "1") (pinfunction "B_1") (pintype "passive"))
      (node (ref "R69") (pin "2") (pinfunction "2_2") (pintype "passive"))
    )
    (net (code "198") (name "Net-(Q63-C)") (class "Default")
      (node (ref "N6") (pin "D2") (pinfunction "D2_D2") (pintype "bidirectional"))
      (node (ref "Q63") (pin "3") (pinfunction "C_3") (pintype "passive"))
    )
    (net (code "199") (name "Net-(Q64-B)") (class "Default")
      (node (ref "Q64") (pin "1") (pinfunction "B_1") (pintype "passive"))
      (node (ref "R70") (pin "2") (pinfunction "2_2") (pintype "passive"))
    )
    (net (code "200") (name "Net-(Q64-C)") (class "Default")
      (node (ref "N6") (pin "D3") (pinfunction "D3_D3") (pintype "bidirectional"))
      (node (ref "Q64") (pin "3") (pinfunction "C_3") (pintype "passive"))
    )
    (net (code "201") (name "Net-(R1-1)") (class "Default")
      (node (ref "N2") (pin "A") (pinfunction "A_A") (pintype "bidirectional"))
      (node (ref "R1") (pin "P$1") (pinfunction "1_P$1") (pintype "passive"))
    )
    (net (code "202") (name "Net-(R2-1)") (class "Default")
      (node (ref "N1") (pin "A") (pinfunction "A_A") (pintype "bidirectional"))
      (node (ref "R2") (pin "P$1") (pinfunction "1_P$1") (pintype "passive"))
    )
    (net (code "203") (name "Net-(R3-1)") (class "Default")
      (node (ref "N5") (pin "A") (pinfunction "A_A") (pintype "bidirectional"))
      (node (ref "R3") (pin "P$1") (pinfunction "1_P$1") (pintype "passive"))
    )
    (net (code "204") (name "Net-(R4-1)") (class "Default")
      (node (ref "N4") (pin "A") (pinfunction "A_A") (pintype "bidirectional"))
      (node (ref "R4") (pin "P$1") (pinfunction "1_P$1") (pintype "passive"))
    )
    (net (code "205") (name "Net-(R5-1)") (class "Default")
      (node (ref "N3") (pin "A") (pinfunction "A_A") (pintype "bidirectional"))
      (node (ref "R5") (pin "P$1") (pinfunction "1_P$1") (pintype "passive"))
    )
    (net (code "206") (name "Net-(R6-1)") (class "Default")
      (node (ref "N6") (pin "A") (pinfunction "A_A") (pintype "bidirectional"))
      (node (ref "R6") (pin "P$1") (pinfunction "1_P$1") (pintype "passive"))
    )
    (net (code "207") (name "VIN") (class "Default")
      (node (ref "JP1") (pin "1") (pinfunction "1_1") (pintype "passive"))
      (node (ref "R1") (pin "P$2") (pinfunction "2_P$2") (pintype "passive"))
      (node (ref "R2") (pin "P$2") (pinfunction "2_P$2") (pintype "passive"))
      (node (ref "R3") (pin "P$2") (pinfunction "2_P$2") (pintype "passive"))
      (node (ref "R4") (pin "P$2") (pinfunction "2_P$2") (pintype "passive"))
      (node (ref "R5") (pin "P$2") (pinfunction "2_P$2") (pintype "passive"))
      (node (ref "R6") (pin "P$2") (pinfunction "2_P$2") (pintype "passive"))
    )
    (net (code "208") (name "unconnected-(IC1A-QH*-Pad9)") (class "Default")
      (node (ref "IC1") (pin "9") (pinfunction "QH*_9") (pintype "tri_state"))
    )
    (net (code "209") (name "unconnected-(N1-PadLHDP)") (class "Default")
      (node (ref "N1") (pin "LHDP") (pinfunction "LHDP_LHDP") (pintype "bidirectional"))
    )
    (net (code "210") (name "unconnected-(N1-PadRHDP)") (class "Default")
      (node (ref "N1") (pin "RHDP") (pinfunction "RHDP_RHDP") (pintype "bidirectional"))
    )
    (net (code "211") (name "unconnected-(N2-PadLHDP)") (class "Default")
      (node (ref "N2") (pin "LHDP") (pinfunction "LHDP_LHDP") (pintype "bidirectional"))
    )
    (net (code "212") (name "unconnected-(N2-PadRHDP)") (class "Default")
      (node (ref "N2") (pin "RHDP") (pinfunction "RHDP_RHDP") (pintype "bidirectional"))
    )
    (net (code "213") (name "unconnected-(N3-PadLHDP)") (class "Default")
      (node (ref "N3") (pin "LHDP") (pinfunction "LHDP_LHDP") (pintype "bidirectional"))
    )
    (net (code "214") (name "unconnected-(N3-PadRHDP)") (class "Default")
      (node (ref "N3") (pin "RHDP") (pinfunction "RHDP_RHDP") (pintype "bidirectional"))
    )
    (net (code "215") (name "unconnected-(N4-PadLHDP)") (class "Default")
      (node (ref "N4") (pin "LHDP") (pinfunction "LHDP_LHDP") (pintype "bidirectional"))
    )
    (net (code "216") (name "unconnected-(N4-PadRHDP)") (class "Default")
      (node (ref "N4") (pin "RHDP") (pinfunction "RHDP_RHDP") (pintype "bidirectional"))
    )
    (net (code "217") (name "unconnected-(N5-PadLHDP)") (class "Default")
      (node (ref "N5") (pin "LHDP") (pinfunction "LHDP_LHDP") (pintype "bidirectional"))
    )
    (net (code "218") (name "unconnected-(N5-PadRHDP)") (class "Default")
      (node (ref "N5") (pin "RHDP") (pinfunction "RHDP_RHDP") (pintype "bidirectional"))
    )
    (net (code "219") (name "unconnected-(N6-PadLHDP)") (class "Default")
      (node (ref "N6") (pin "LHDP") (pinfunction "LHDP_LHDP") (pintype "bidirectional"))
    )
    (net (code "220") (name "unconnected-(N6-PadRHDP)") (class "Default")
      (node (ref "N6") (pin "RHDP") (pinfunction "RHDP_RHDP") (pintype "bidirectional"))
    )
    (net (code "221") (name "unconnected-(Q19-C-Pad3)") (class "Default")
      (node (ref "Q19") (pin "3") (pinfunction "C_3") (pintype "passive"))
    )
    (net (code "222") (name "unconnected-(Q20-C-Pad3)") (class "Default")
      (node (ref "Q20") (pin "3") (pinfunction "C_3") (pintype "passive"))
    )
    (net (code "223") (name "unconnected-(Q45-C-Pad3)") (class "Default")
      (node (ref "Q45") (pin "3") (pinfunction "C_3") (pintype "passive"))
    )
    (net (code "224") (name "unconnected-(Q46-C-Pad3)") (class "Default")
      (node (ref "Q46") (pin "3") (pinfunction "C_3") (pintype "passive"))
    )
  )
)
